# 05004586_2_PIS___2_BHC-A-2030-05__V1_0.net
KiCad netlist of a schematic drawn in Altium Designer
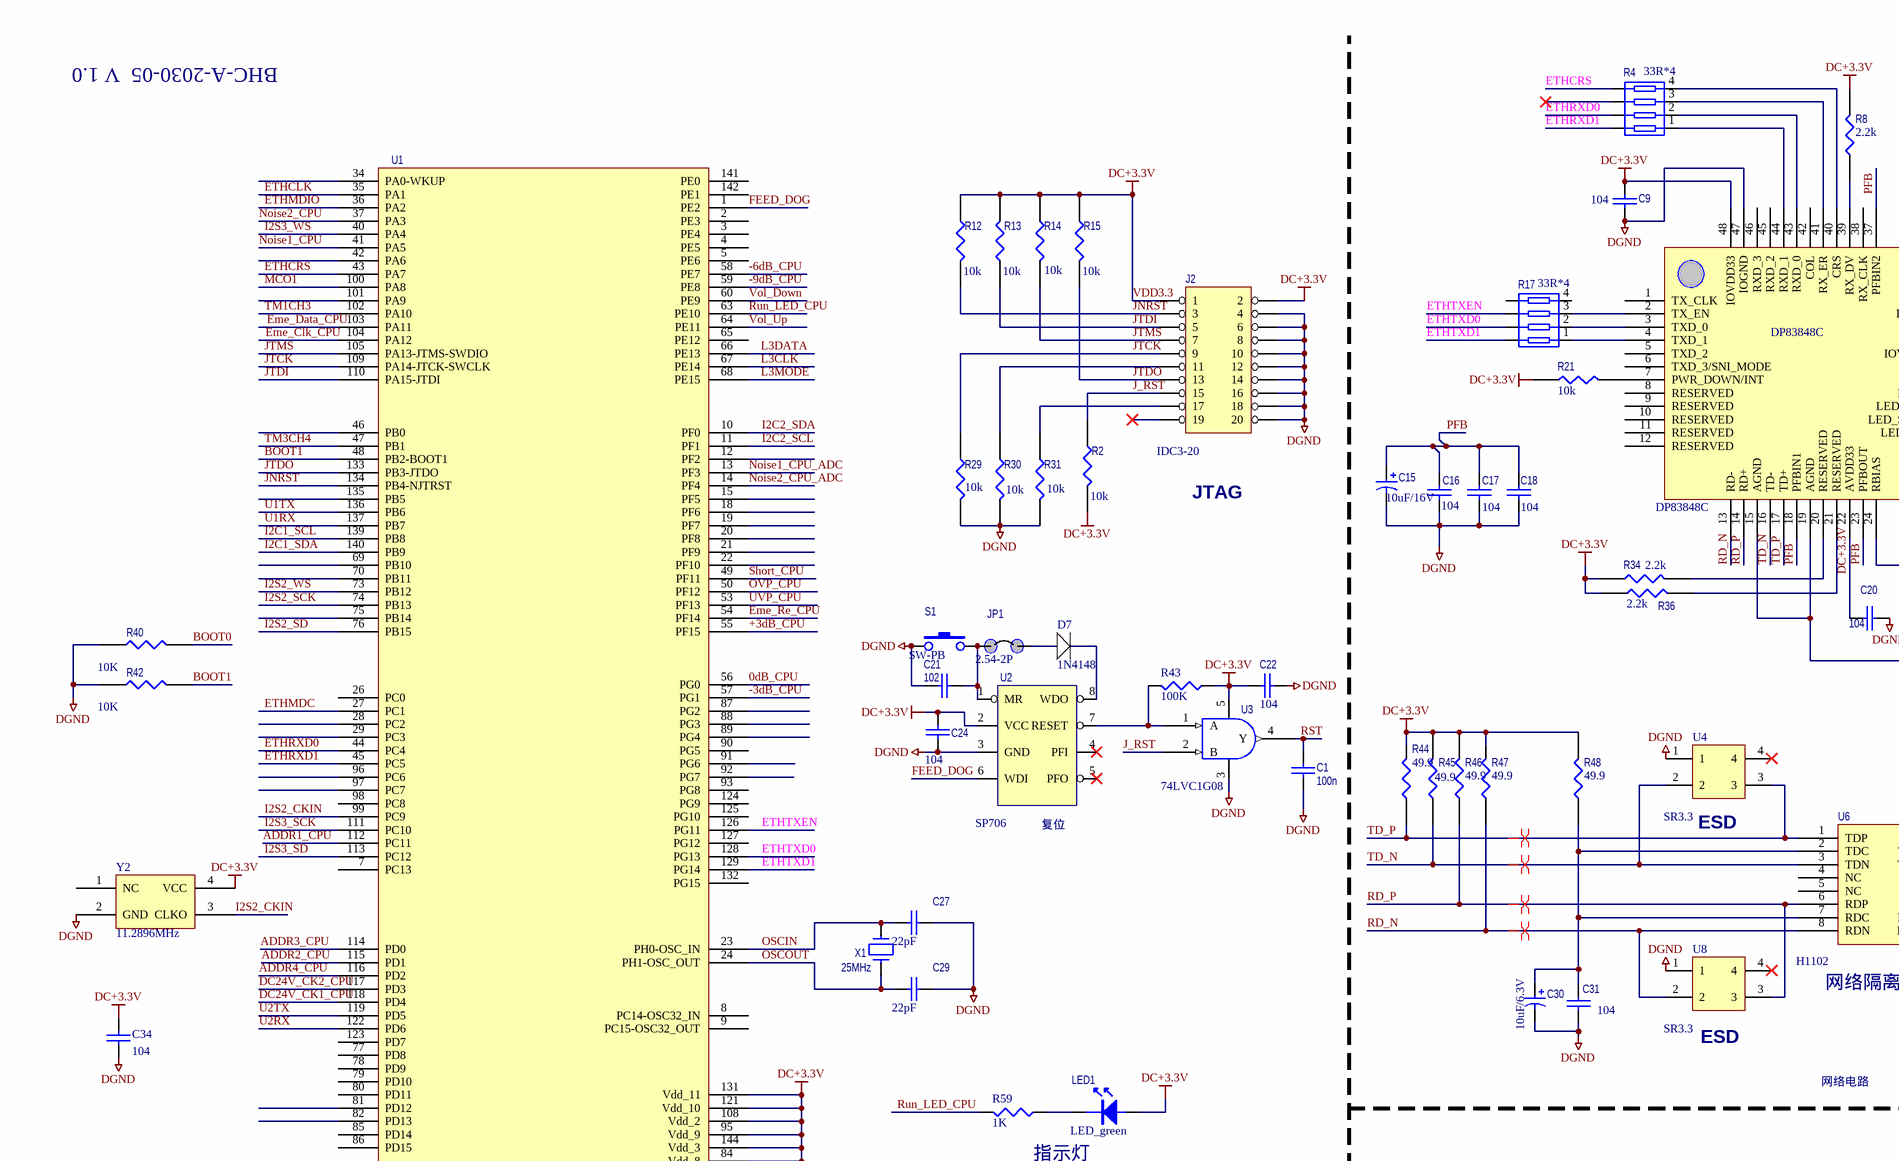
[diagram p0: 05004586宁波2号线二期车载PIS系统_功率放大器音频板2 BHC-A-2030-05_原理图 V1.0.SchDoc, top left]
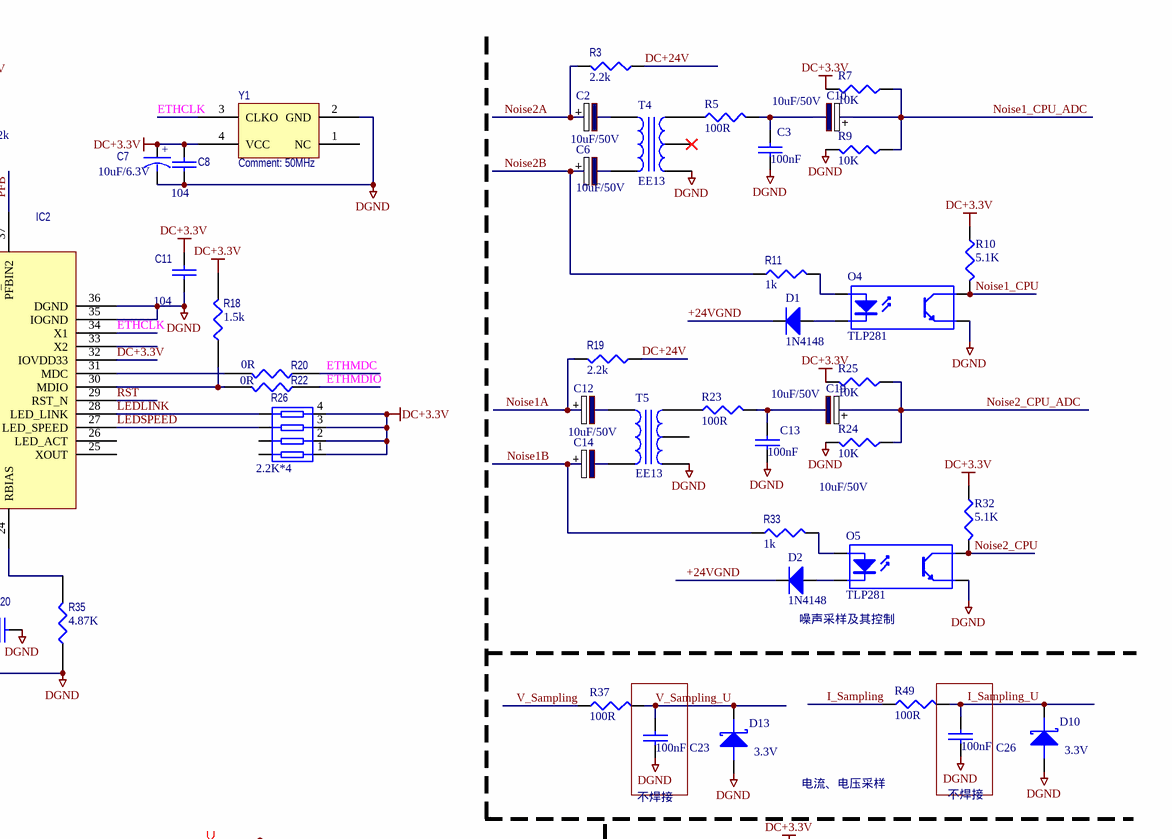
[diagram p1: 05004586宁波2号线二期车载PIS系统_功率放大器音频板2 BHC-A-2030-05_原理图 V1.0.SchDoc, top right]
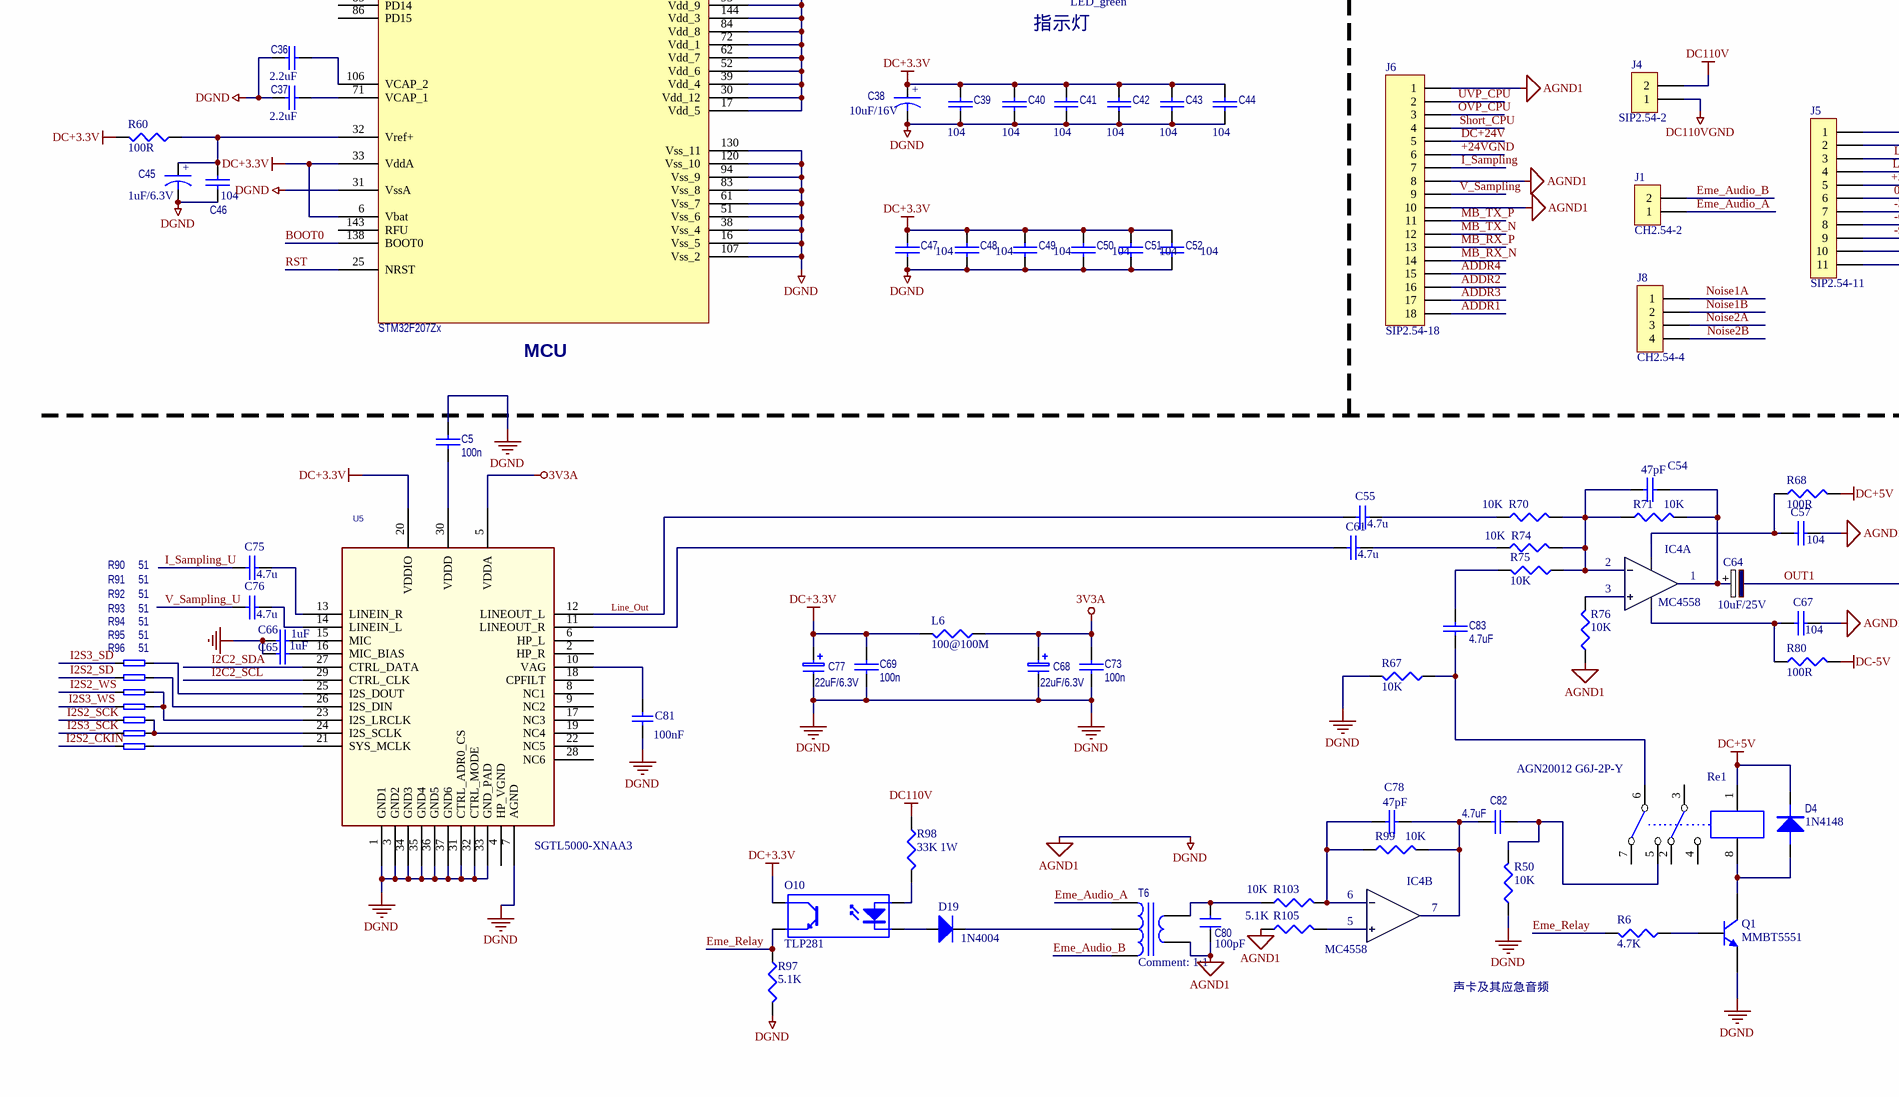
[diagram p2: 05004586宁波2号线二期车载PIS系统_功率放大器音频板2 BHC-A-2030-05_原理图 V1.0.SchDoc, bottom left]
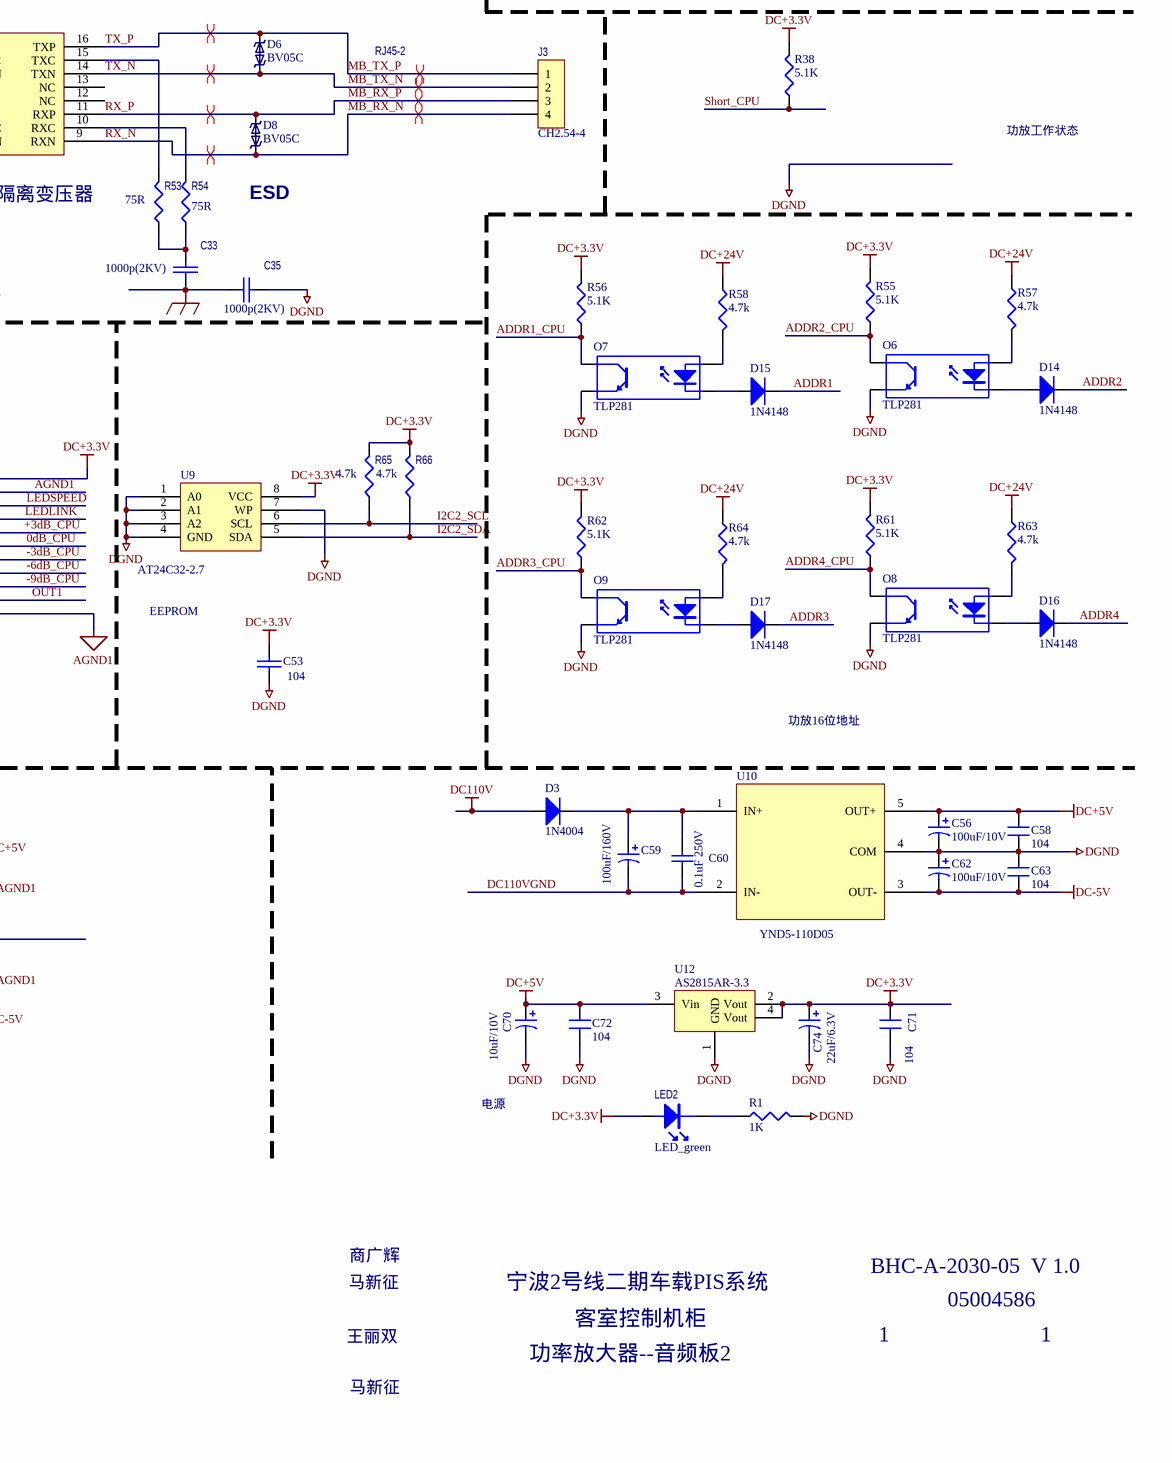
[diagram p3: 05004586宁波2号线二期车载PIS系统_功率放大器音频板2 BHC-A-2030-05_原理图 V1.0.SchDoc, bottom right]

(export (version "E")
  (design (tool "Eeschema 10.0.6"))
  (components
    (comp (ref "C1")
      (value "100n")
      (footprint "C0805")
      (description "Capacitor")
      (libsource (lib "") (part "CAP_4"))
    )
    (comp (ref "C2")
      (value "10uF/50V")
      (footprint "RB1/2")
      (fields (field (name "Comment") "10uF/25V"))
      (libsource (lib "") (part "E_1"))
    )
    (comp (ref "C3")
      (value "100nF")
      (footprint "C0805")
      (description "Capacitor")
      (libsource (lib "") (part "CAP_4"))
    )
    (comp (ref "C5")
      (value "100n")
      (footprint "C0805")
      (description "Capacitor")
      (libsource (lib "") (part "CAP_4"))
    )
    (comp (ref "C6")
      (value "10uF/50V")
      (footprint "RB1/2")
      (fields (field (name "Comment") "10uF/25V"))
      (libsource (lib "") (part "E_1"))
    )
    (comp (ref "C7")
      (value "10uF/6.3V")
      (footprint "3216A")
      (description "Capacitor")
      (libsource (lib "*") (part "CAPACITOR POL"))
    )
    (comp (ref "C8")
      (value "104")
      (footprint "C0805")
      (description "Capacitor")
      (libsource (lib "") (part "CAP_1"))
    )
    (comp (ref "C9")
      (value "104")
      (footprint "C0805")
      (description "Capacitor")
      (libsource (lib "") (part "CAP_1"))
    )
    (comp (ref "C10")
      (value "10uF/50V")
      (footprint "RB1/2")
      (fields (field (name "Comment") "10uF/25V"))
      (libsource (lib "*") (part "E"))
    )
    (comp (ref "C11")
      (value "104")
      (footprint "C0805")
      (description "Capacitor")
      (libsource (lib "") (part "CAP_1"))
    )
    (comp (ref "C12")
      (value "10uF/50V")
      (footprint "RB1/2")
      (fields (field (name "Comment") "10uF/25V"))
      (libsource (lib "") (part "E_1"))
    )
    (comp (ref "C13")
      (value "100nF")
      (footprint "C0805")
      (description "Capacitor")
      (libsource (lib "") (part "CAP_4"))
    )
    (comp (ref "C14")
      (value "10uF/50V")
      (footprint "RB1/2")
      (fields (field (name "Comment") "10uF/25V"))
      (libsource (lib "") (part "E_1"))
    )
    (comp (ref "C15")
      (value "10uF/16V")
      (footprint "CAP-B")
      (description "Bi-Polar Capacitor")
      (libsource (lib "*") (part "CAP2"))
    )
    (comp (ref "C16")
      (value "104")
      (footprint "C0805")
      (description "Capacitor")
      (libsource (lib "") (part "CAP_1"))
    )
    (comp (ref "C17")
      (value "104")
      (footprint "C0805")
      (description "Capacitor")
      (libsource (lib "") (part "CAP_1"))
    )
    (comp (ref "C18")
      (value "104")
      (footprint "C0805")
      (description "Capacitor")
      (libsource (lib "") (part "CAP_1"))
    )
    (comp (ref "C19")
      (value "10uF/50V")
      (footprint "RB1/2")
      (fields (field (name "Comment") "10uF/25V"))
      (libsource (lib "*") (part "E"))
    )
    (comp (ref "C20")
      (value "104")
      (footprint "C0805")
      (description "Capacitor")
      (libsource (lib "") (part "CAP_1"))
    )
    (comp (ref "C21")
      (value "102")
      (footprint "C0805")
      (description "Capacitor")
      (libsource (lib "") (part "CAP_2"))
    )
    (comp (ref "C22")
      (value "104")
      (footprint "C0805")
      (description "Capacitor")
      (libsource (lib "") (part "CAP_2"))
    )
    (comp (ref "C23")
      (value "100nF")
      (footprint "C0805")
      (description "Capacitor")
      (libsource (lib "") (part "CAP_4"))
    )
    (comp (ref "C24")
      (value "104")
      (footprint "C0805")
      (description "Capacitor")
      (libsource (lib "") (part "CAP_2"))
    )
    (comp (ref "C26")
      (value "100nF")
      (footprint "C0805")
      (description "Capacitor")
      (libsource (lib "") (part "CAP_4"))
    )
    (comp (ref "C27")
      (value "22pF")
      (footprint "C0805")
      (description "Capacitor")
      (libsource (lib "") (part "CAP_1"))
    )
    (comp (ref "C29")
      (value "22pF")
      (footprint "C0805")
      (description "Capacitor")
      (libsource (lib "") (part "CAP_1"))
    )
    (comp (ref "C30")
      (value "10uF/6.3V")
      (footprint "3216A")
      (description "Bi-Polar Capacitor")
      (fields (field (name "Comment") "10uF/10V"))
      (libsource (lib "*") (part "CAP2"))
    )
    (comp (ref "C31") (value "104") (footprint "C0805") (libsource (lib "*") (part "CAP")))
    (comp (ref "C33")
      (value "1000p(2KV)")
      (footprint "C1206")
      (description "Capacitor")
      (fields (field (name "ALTIUM_UNNAMED_1") "1000p(2KV)"))
      (libsource (lib "") (part "CAP_1"))
    )
    (comp (ref "C34") (value "104") (footprint "C0805") (libsource (lib "*") (part "CAP")))
    (comp (ref "C35")
      (value "1000p(2KV)")
      (footprint "C1206")
      (description "Capacitor")
      (fields (field (name "ALTIUM_UNNAMED_1") "1000p(2KV)"))
      (libsource (lib "") (part "CAP_1"))
    )
    (comp (ref "C36")
      (value "2.2uF")
      (footprint "C0805")
      (description "Capacitor")
      (libsource (lib "") (part "CAP_1"))
    )
    (comp (ref "C37")
      (value "2.2uF")
      (footprint "C0805")
      (description "Capacitor")
      (libsource (lib "") (part "CAP_1"))
    )
    (comp (ref "C38")
      (value "10uF/16V")
      (footprint "CAP-B")
      (description "Capacitor")
      (libsource (lib "*") (part "CAPACITOR POL"))
    )
    (comp (ref "C39") (value "104") (footprint "C0805") (libsource (lib "*") (part "CAP")))
    (comp (ref "C40") (value "104") (footprint "C0805") (libsource (lib "*") (part "CAP")))
    (comp (ref "C41") (value "104") (footprint "C0805") (libsource (lib "*") (part "CAP")))
    (comp (ref "C42") (value "104") (footprint "C0805") (libsource (lib "*") (part "CAP")))
    (comp (ref "C43") (value "104") (footprint "C0805") (libsource (lib "*") (part "CAP")))
    (comp (ref "C44") (value "104") (footprint "C0805") (libsource (lib "*") (part "CAP")))
    (comp (ref "C45")
      (value "1uF/6.3V")
      (footprint "3216A")
      (description "Capacitor")
      (libsource (lib "*") (part "CAPACITOR POL"))
    )
    (comp (ref "C46")
      (value "104")
      (footprint "C0805")
      (description "Capacitor")
      (libsource (lib "") (part "CAP_1"))
    )
    (comp (ref "C47") (value "104") (footprint "C0805") (libsource (lib "*") (part "CAP")))
    (comp (ref "C48") (value "104") (footprint "C0805") (libsource (lib "*") (part "CAP")))
    (comp (ref "C49") (value "104") (footprint "C0805") (libsource (lib "*") (part "CAP")))
    (comp (ref "C50") (value "104") (footprint "C0805") (libsource (lib "*") (part "CAP")))
    (comp (ref "C51") (value "104") (footprint "C0805") (libsource (lib "*") (part "CAP")))
    (comp (ref "C52") (value "104") (footprint "C0805") (libsource (lib "*") (part "CAP")))
    (comp (ref "C53")
      (value "104")
      (footprint "C0805")
      (description "Capacitor")
      (libsource (lib "") (part "CAP_2"))
    )
    (comp (ref "C54")
      (value "47pF")
      (footprint "C0805")
      (description "Capacitor")
      (libsource (lib "") (part "CAP_4"))
    )
    (comp (ref "C55")
      (value "4.7u")
      (footprint "C0805")
      (description "Capacitor")
      (fields (field (name "Comment") "104"))
      (libsource (lib "") (part "CAP_4"))
    )
    (comp (ref "C56")
      (value "100uF/10V")
      (footprint "CAP-D")
      (description "Bi-Polar Capacitor")
      (fields (field (name "Comment") "100uF/16V"))
      (libsource (lib "*") (part "CAP2"))
    )
    (comp (ref "C57")
      (value "104")
      (footprint "C0805")
      (description "Capacitor")
      (libsource (lib "") (part "CAP_4"))
    )
    (comp (ref "C58")
      (value "104")
      (footprint "C0805")
      (description "Capacitor")
      (libsource (lib "") (part "CAP_3"))
    )
    (comp (ref "C59")
      (value "100uF/160V")
      (footprint "E100")
      (description "Bi-Polar Capacitor")
      (fields (field (name "Comment") "100uF/16V"))
      (libsource (lib "*") (part "CAP2"))
    )
    (comp (ref "C60")
      (value "0.1uF 250V")
      (footprint "M1206")
      (description "Capacitor")
      (fields (field (name "PUBLISHER") "Altium Limited"))
      (libsource (lib "*") (part "Cap"))
    )
    (comp (ref "C61")
      (value "4.7u")
      (footprint "C0805")
      (description "Capacitor")
      (fields (field (name "Comment") "104"))
      (libsource (lib "") (part "CAP_4"))
    )
    (comp (ref "C62")
      (value "100uF/10V")
      (footprint "CAP-D")
      (description "Bi-Polar Capacitor")
      (fields (field (name "Comment") "100uF/16V"))
      (libsource (lib "*") (part "CAP2"))
    )
    (comp (ref "C63")
      (value "104")
      (footprint "C0805")
      (description "Capacitor")
      (libsource (lib "") (part "CAP_3"))
    )
    (comp (ref "C64") (value "10uF/25V") (footprint "RB1/2") (libsource (lib "") (part "E_1")))
    (comp (ref "C65")
      (value "1uF")
      (footprint "C0805")
      (description "Capacitor")
      (fields (field (name "PUBLISHER") "Altium Limited"))
      (libsource (lib "Miscellaneous Devices") (part "Cap"))
    )
    (comp (ref "C66")
      (value "1uF")
      (footprint "C0805")
      (description "Capacitor")
      (fields (field (name "PUBLISHER") "Altium Limited"))
      (libsource (lib "Miscellaneous Devices") (part "Cap"))
    )
    (comp (ref "C67")
      (value "104")
      (footprint "C0805")
      (description "Capacitor")
      (libsource (lib "") (part "CAP_4"))
    )
    (comp (ref "C68")
      (value "22uF/6.3V")
      (footprint "3216A")
      (description "Bi-Polar Capacitor")
      (libsource (lib "*") (part "CAPBP2"))
    )
    (comp (ref "C69")
      (value "100n")
      (footprint "C0805")
      (description "Capacitor")
      (libsource (lib "") (part "CAP_4"))
    )
    (comp (ref "C70")
      (value "10uF/10V")
      (footprint "3216A")
      (description "Bi-Polar Capacitor")
      (libsource (lib "*") (part "CAP2"))
    )
    (comp (ref "C71")
      (value "104")
      (footprint "C0805")
      (description "Capacitor")
      (libsource (lib "") (part "CAP_3"))
    )
    (comp (ref "C72")
      (value "104")
      (footprint "C0805")
      (description "Capacitor")
      (libsource (lib "") (part "CAP_3"))
    )
    (comp (ref "C73")
      (value "100n")
      (footprint "C0805")
      (description "Capacitor")
      (libsource (lib "") (part "CAP_4"))
    )
    (comp (ref "C74")
      (value "22uF/6.3V")
      (footprint "3216A")
      (description "Bi-Polar Capacitor")
      (libsource (lib "*") (part "CAP2"))
    )
    (comp (ref "C75")
      (value "4.7u")
      (footprint "C0805")
      (description "Capacitor")
      (fields (field (name "Comment") "104"))
      (libsource (lib "") (part "CAP_4"))
    )
    (comp (ref "C76")
      (value "4.7u")
      (footprint "C0805")
      (description "Capacitor")
      (fields (field (name "Comment") "104"))
      (libsource (lib "") (part "CAP_4"))
    )
    (comp (ref "C77")
      (value "22uF/6.3V")
      (footprint "3216A")
      (description "Bi-Polar Capacitor")
      (libsource (lib "*") (part "CAPBP2"))
    )
    (comp (ref "C78")
      (value "47pF")
      (footprint "C0805")
      (description "Capacitor")
      (libsource (lib "") (part "CAP_4"))
    )
    (comp (ref "C80")
      (value "100pF")
      (footprint "C0805")
      (description "Capacitor")
      (fields (field (name "Comment") "100p"))
      (libsource (lib "") (part "CAP_3"))
    )
    (comp (ref "C81")
      (value "100nF")
      (footprint "C0805")
      (description "Capacitor")
      (fields (field (name "Comment") "100n") (field (name "PUBLISHER") "Altium Limited"))
      (libsource (lib "Miscellaneous Devices") (part "Cap"))
    )
    (comp (ref "C82")
      (value "4.7uF")
      (footprint "C0805")
      (description "Capacitor")
      (libsource (lib "") (part "CAP_4"))
    )
    (comp (ref "C83")
      (value "4.7uF")
      (footprint "C0805")
      (description "Capacitor")
      (libsource (lib "") (part "CAP_4"))
    )
    (comp (ref "D1")
      (value "1N4148")
      (footprint "7227AK")
      (description "Default Diode")
      (fields (field (name "Comment") "DIODE"))
      (libsource (lib "SCH") (part "DIODE"))
    )
    (comp (ref "D2")
      (value "1N4148")
      (footprint "7227AK")
      (description "Default Diode")
      (fields (field (name "Comment") "DIODE"))
      (libsource (lib "SCH") (part "DIODE"))
    )
    (comp (ref "D3")
      (value "1N4004")
      (footprint "7227AK")
      (description "Default Diode")
      (fields (field (name "Comment") "DIODE"))
      (libsource (lib "SCH") (part "DIODE"))
    )
    (comp (ref "D4")
      (value "1N4148")
      (footprint "7227AK")
      (description "Diode")
      (fields (field (name "Comment") "1N4004"))
      (libsource (lib "*") (part "DIODE"))
    )
    (comp (ref "D6") (value "BV05C") (footprint "SOD-323") (libsource (lib "Sch") (part "BV05C")))
    (comp (ref "D7") (value "1N4148") (footprint "1206AK") (libsource (lib "*") (part "D")))
    (comp (ref "D8") (value "BV05C") (footprint "SOD-323") (libsource (lib "Sch") (part "BV05C")))
    (comp (ref "D10")
      (value "3.3V")
      (footprint "1206ak")
      (description "Schottky Diode")
      (libsource (lib "*") (part "DIODE SCHOTTKY"))
    )
    (comp (ref "D13")
      (value "3.3V")
      (footprint "1206ak")
      (description "Schottky Diode")
      (libsource (lib "*") (part "DIODE SCHOTTKY"))
    )
    (comp (ref "D14")
      (value "1N4148")
      (footprint "7227AK")
      (description "Default Diode")
      (fields (field (name "Comment") "DIODE"))
      (libsource (lib "SCH") (part "DIODE"))
    )
    (comp (ref "D15")
      (value "1N4148")
      (footprint "7227AK")
      (description "Default Diode")
      (fields (field (name "Comment") "DIODE"))
      (libsource (lib "SCH") (part "DIODE"))
    )
    (comp (ref "D16")
      (value "1N4148")
      (footprint "7227AK")
      (description "Default Diode")
      (fields (field (name "Comment") "DIODE"))
      (libsource (lib "SCH") (part "DIODE"))
    )
    (comp (ref "D17")
      (value "1N4148")
      (footprint "7227AK")
      (description "Default Diode")
      (fields (field (name "Comment") "DIODE"))
      (libsource (lib "SCH") (part "DIODE"))
    )
    (comp (ref "D19")
      (value "1N4004")
      (footprint "7227AK")
      (description "Default Diode")
      (fields (field (name "Comment") "DIODE"))
      (libsource (lib "SCH") (part "DIODE"))
    )
    (comp (ref "IC2") (value "DP83848C") (footprint "LQFP48") (libsource (lib "*") (part "DP83848C")))
    (comp (ref "IC4") (value "MC4558") (footprint "SO-8") (libsource (lib "*") (part "MC4558")))
    (comp (ref "J1")
      (value "CH2.54-2")
      (footprint "CH2.54-2")
      (description "Connector")
      (fields (field (name "Comment") "CON2"))
      (libsource (lib "SCH") (part "CON2"))
    )
    (comp (ref "J2")
      (value "IDC3-20")
      (footprint "IDC3-20")
      (fields (field (name "Comment") "IDC20"))
      (libsource (lib "*") (part "HEADER 10X2"))
    )
    (comp (ref "J3")
      (value "CH2.54-4")
      (footprint "CH2.54-4")
      (description "Connector")
      (fields (field (name "Comment") "CON4"))
      (libsource (lib "*") (part "CON4"))
    )
    (comp (ref "J4")
      (value "SIP2.54-2")
      (footprint "SIP2.54-2")
      (description "Connector")
      (fields (field (name "Comment") "CON2"))
      (libsource (lib "SCH") (part "CON2"))
    )
    (comp (ref "J5")
      (value "SIP2.54-11")
      (footprint "SIP2.54-11")
      (fields (field (name "Comment") "CON11"))
      (libsource (lib "SCH") (part "CON11"))
    )
    (comp (ref "J6")
      (value "SIP2.54-18")
      (footprint "SIP2.54-18")
      (description "Connector")
      (fields (field (name "Comment") "CON18"))
      (libsource (lib "SCH") (part "CON18"))
    )
    (comp (ref "J8")
      (value "CH2.54-4")
      (footprint "CH2.54-4")
      (fields (field (name "Comment") "CON4"))
      (libsource (lib "SCH") (part "CON4"))
    )
    (comp (ref "JP1") (value "2.54-2P") (footprint "SIP2.54-2") (libsource (lib "*") (part "TX")))
    (comp (ref "L6")
      (value "100@100M")
      (footprint "M0805")
      (description "Resistor")
      (fields (field (name "Comment") "10uH") (field (name "PUBLISHER") "Altium Limited"))
      (libsource (lib "Miscellaneous Devices") (part "Res3"))
    )
    (comp (ref "LED1") (value "LED_green") (footprint "LED(贴片)") (libsource (lib "*") (part "LED")))
    (comp (ref "LED2") (value "LED_green") (footprint "LED(贴片)") (libsource (lib "*") (part "LED")))
    (comp (ref "O4")
      (value "TLP281")
      (footprint "SOP4")
      (description "4-Pin Phototransistor Optocoupler")
      (fields (field (name "PUBLISHER") "Altium Limited"))
      (libsource (lib "Miscellaneous Devices") (part "Optoisolator1"))
    )
    (comp (ref "O5")
      (value "TLP281")
      (footprint "SOP4")
      (description "4-Pin Phototransistor Optocoupler")
      (fields (field (name "PUBLISHER") "Altium Limited"))
      (libsource (lib "Miscellaneous Devices") (part "Optoisolator1"))
    )
    (comp (ref "O6")
      (value "TLP281")
      (footprint "SOP4")
      (description "4-Pin Phototransistor Optocoupler")
      (fields (field (name "PUBLISHER") "Altium Limited"))
      (libsource (lib "Miscellaneous Devices") (part "Optoisolator1"))
    )
    (comp (ref "O7")
      (value "TLP281")
      (footprint "SOP4")
      (description "4-Pin Phototransistor Optocoupler")
      (fields (field (name "PUBLISHER") "Altium Limited"))
      (libsource (lib "Miscellaneous Devices") (part "Optoisolator1"))
    )
    (comp (ref "O8")
      (value "TLP281")
      (footprint "SOP4")
      (description "4-Pin Phototransistor Optocoupler")
      (fields (field (name "PUBLISHER") "Altium Limited"))
      (libsource (lib "Miscellaneous Devices") (part "Optoisolator1"))
    )
    (comp (ref "O9")
      (value "TLP281")
      (footprint "SOP4")
      (description "4-Pin Phototransistor Optocoupler")
      (fields (field (name "PUBLISHER") "Altium Limited"))
      (libsource (lib "Miscellaneous Devices") (part "Optoisolator1"))
    )
    (comp (ref "O10")
      (value "TLP281")
      (footprint "SOP4")
      (description "4-Pin Phototransistor Optocoupler")
      (fields (field (name "PUBLISHER") "Altium Limited"))
      (libsource (lib "Miscellaneous Devices") (part "Optoisolator1"))
    )
    (comp (ref "Q1")
      (value "MMBT5551")
      (footprint "SOT-23B_N")
      (description "NPN Bipolar Transistor")
      (fields (field (name "PUBLISHER") "Altium Limited"))
      (libsource (lib "*") (part "NPN"))
    )
    (comp (ref "R1")
      (value "1K")
      (footprint "M0805")
      (description "Resistor")
      (fields (field (name "PUBLISHER") "Altium Limited"))
      (libsource (lib "*") (part "Res3"))
    )
    (comp (ref "R2")
      (value "10k")
      (footprint "M0805")
      (fields (field (name "Comment") "10K"))
      (libsource (lib "*") (part "RES1"))
    )
    (comp (ref "R3") (value "2.2k") (footprint "M0805") (libsource (lib "") (part "RES1_1")))
    (comp (ref "R4")
      (value "33R*4")
      (footprint "PZ-4-0.8B")
      (fields (field (name "Comment") "33*4"))
      (libsource (lib "*") (part "RES-P4"))
    )
    (comp (ref "R5")
      (value "100R")
      (footprint "M0805")
      (description "Resistor")
      (fields (field (name "PUBLISHER") "Altium Limited"))
      (libsource (lib "*") (part "Res3"))
    )
    (comp (ref "R6")
      (value "4.7K")
      (footprint "M0805")
      (description "Resistor")
      (fields (field (name "Comment") "Res3") (field (name "PUBLISHER") "Altium Limited"))
      (libsource (lib "Miscellaneous Devices") (part "Res3"))
    )
    (comp (ref "R7")
      (value "10K")
      (footprint "M0805")
      (description "Resistor")
      (fields (field (name "PUBLISHER") "Altium Limited"))
      (libsource (lib "*") (part "Res3"))
    )
    (comp (ref "R8")
      (value "2.2k")
      (footprint "M0805")
      (fields (field (name "Comment") "10K"))
      (libsource (lib "*") (part "RES1"))
    )
    (comp (ref "R9")
      (value "10K")
      (footprint "M0805")
      (description "Resistor")
      (fields (field (name "PUBLISHER") "Altium Limited"))
      (libsource (lib "*") (part "Res3"))
    )
    (comp (ref "R10")
      (value "5.1K")
      (footprint "M0805")
      (description "Resistor")
      (fields (field (name "PUBLISHER") "Altium Limited"))
      (libsource (lib "*") (part "Res3"))
    )
    (comp (ref "R11") (value "1k") (footprint "M0805") (libsource (lib "") (part "RES1_1")))
    (comp (ref "R12")
      (value "10k")
      (footprint "M0805")
      (fields (field (name "Comment") "10K"))
      (libsource (lib "*") (part "RES1"))
    )
    (comp (ref "R13")
      (value "10k")
      (footprint "M0805")
      (fields (field (name "Comment") "10K"))
      (libsource (lib "*") (part "RES1"))
    )
    (comp (ref "R14")
      (value "10k")
      (footprint "M0805")
      (fields (field (name "Comment") "10K"))
      (libsource (lib "*") (part "RES1"))
    )
    (comp (ref "R15")
      (value "10k")
      (footprint "M0805")
      (fields (field (name "Comment") "10K"))
      (libsource (lib "*") (part "RES1"))
    )
    (comp (ref "R17")
      (value "33R*4")
      (footprint "PZ-4-0.8B")
      (fields (field (name "Comment") "33*4"))
      (libsource (lib "*") (part "RES-P4"))
    )
    (comp (ref "R18")
      (value "1.5k")
      (footprint "M0805")
      (fields (field (name "Comment") "10K"))
      (libsource (lib "*") (part "RES1"))
    )
    (comp (ref "R19") (value "2.2k") (footprint "M0805") (libsource (lib "") (part "RES1_1")))
    (comp (ref "R20") (value "0R") (footprint "M0805") (libsource (lib "*") (part "RES1")))
    (comp (ref "R21")
      (value "10k")
      (footprint "M0805")
      (fields (field (name "Comment") "10K"))
      (libsource (lib "*") (part "RES1"))
    )
    (comp (ref "R22") (value "0R") (footprint "M0805") (libsource (lib "*") (part "RES1")))
    (comp (ref "R23")
      (value "100R")
      (footprint "M0805")
      (description "Resistor")
      (fields (field (name "PUBLISHER") "Altium Limited"))
      (libsource (lib "*") (part "Res3"))
    )
    (comp (ref "R24")
      (value "10K")
      (footprint "M0805")
      (description "Resistor")
      (fields (field (name "PUBLISHER") "Altium Limited"))
      (libsource (lib "*") (part "Res3"))
    )
    (comp (ref "R25")
      (value "10K")
      (footprint "M0805")
      (description "Resistor")
      (fields (field (name "PUBLISHER") "Altium Limited"))
      (libsource (lib "*") (part "Res3"))
    )
    (comp (ref "R26")
      (value "~")
      (footprint "PZ-4-0.8B")
      (fields (field (name "ALTIUM_UNNAMED_1") "2.2K*4"))
      (libsource (lib "*") (part "RES-P4"))
    )
    (comp (ref "R29")
      (value "10k")
      (footprint "M0805")
      (fields (field (name "Comment") "10K"))
      (libsource (lib "*") (part "RES1"))
    )
    (comp (ref "R30")
      (value "10k")
      (footprint "M0805")
      (fields (field (name "Comment") "10K"))
      (libsource (lib "*") (part "RES1"))
    )
    (comp (ref "R31")
      (value "10k")
      (footprint "M0805")
      (fields (field (name "Comment") "10K"))
      (libsource (lib "*") (part "RES1"))
    )
    (comp (ref "R32")
      (value "5.1K")
      (footprint "M0805")
      (description "Resistor")
      (fields (field (name "PUBLISHER") "Altium Limited"))
      (libsource (lib "*") (part "Res3"))
    )
    (comp (ref "R33") (value "1k") (footprint "M0805") (libsource (lib "") (part "RES1_1")))
    (comp (ref "R34")
      (value "2.2k")
      (footprint "M0805")
      (fields (field (name "Comment") "10K"))
      (libsource (lib "*") (part "RES1"))
    )
    (comp (ref "R35") (value "4.87K") (footprint "M0805") (libsource (lib "*") (part "RES1")))
    (comp (ref "R36")
      (value "2.2k")
      (footprint "M0805")
      (fields (field (name "Comment") "10K"))
      (libsource (lib "*") (part "RES1"))
    )
    (comp (ref "R37")
      (value "100R")
      (footprint "M0805")
      (description "Resistor")
      (fields (field (name "PUBLISHER") "Altium Limited"))
      (libsource (lib "*") (part "Res3"))
    )
    (comp (ref "R38")
      (value "5.1K")
      (footprint "M0805")
      (description "Resistor")
      (fields (field (name "PUBLISHER") "Altium Limited"))
      (libsource (lib "*") (part "Res3"))
    )
    (comp (ref "R40") (value "10K") (footprint "M0805") (libsource (lib "*") (part "RES1")))
    (comp (ref "R42") (value "10K") (footprint "M0805") (libsource (lib "*") (part "RES1")))
    (comp (ref "R43")
      (value "100K")
      (footprint "M0805")
      (description "Resistor")
      (fields (field (name "PUBLISHER") "Altium Limited"))
      (libsource (lib "*") (part "Res3"))
    )
    (comp (ref "R44") (value "49.9") (footprint "M0805") (libsource (lib "*") (part "RES1")))
    (comp (ref "R45") (value "49.9") (footprint "M0805") (libsource (lib "*") (part "RES1")))
    (comp (ref "R46") (value "49.9") (footprint "M0805") (libsource (lib "*") (part "RES1")))
    (comp (ref "R47") (value "49.9") (footprint "M0805") (libsource (lib "*") (part "RES1")))
    (comp (ref "R48") (value "49.9") (footprint "M0805") (libsource (lib "*") (part "RES1")))
    (comp (ref "R49")
      (value "100R")
      (footprint "M0805")
      (description "Resistor")
      (fields (field (name "PUBLISHER") "Altium Limited"))
      (libsource (lib "*") (part "Res3"))
    )
    (comp (ref "R50")
      (value "10K")
      (footprint "M0805")
      (description "Resistor")
      (fields (field (name "Comment") "10k") (field (name "PUBLISHER") "Altium Limited"))
      (libsource (lib "Miscellaneous Devices") (part "Res3"))
    )
    (comp (ref "R53") (value "75R") (footprint "M0805") (libsource (lib "") (part "RES1_1")))
    (comp (ref "R54") (value "75R") (footprint "M0805") (libsource (lib "") (part "RES1_1")))
    (comp (ref "R55")
      (value "5.1K")
      (footprint "M0805")
      (description "Resistor")
      (fields (field (name "PUBLISHER") "Altium Limited"))
      (libsource (lib "*") (part "Res3"))
    )
    (comp (ref "R56")
      (value "5.1K")
      (footprint "M0805")
      (description "Resistor")
      (fields (field (name "PUBLISHER") "Altium Limited"))
      (libsource (lib "*") (part "Res3"))
    )
    (comp (ref "R57")
      (value "4.7k")
      (footprint "M1206")
      (description "Resistor")
      (fields (field (name "PUBLISHER") "Altium Limited"))
      (libsource (lib "Miscellaneous Devices") (part "Res3"))
    )
    (comp (ref "R58")
      (value "4.7k")
      (footprint "M1206")
      (description "Resistor")
      (fields (field (name "PUBLISHER") "Altium Limited"))
      (libsource (lib "Miscellaneous Devices") (part "Res3"))
    )
    (comp (ref "R59")
      (value "1K")
      (footprint "M0805")
      (description "Resistor")
      (fields (field (name "PUBLISHER") "Altium Limited"))
      (libsource (lib "*") (part "Res3"))
    )
    (comp (ref "R60")
      (value "100R")
      (footprint "M0805")
      (description "Resistor")
      (fields (field (name "PUBLISHER") "Altium Limited"))
      (libsource (lib "*") (part "Res3"))
    )
    (comp (ref "R61")
      (value "5.1K")
      (footprint "M0805")
      (description "Resistor")
      (fields (field (name "PUBLISHER") "Altium Limited"))
      (libsource (lib "*") (part "Res3"))
    )
    (comp (ref "R62")
      (value "5.1K")
      (footprint "M0805")
      (description "Resistor")
      (fields (field (name "PUBLISHER") "Altium Limited"))
      (libsource (lib "*") (part "Res3"))
    )
    (comp (ref "R63")
      (value "4.7k")
      (footprint "M1206")
      (description "Resistor")
      (fields (field (name "PUBLISHER") "Altium Limited"))
      (libsource (lib "Miscellaneous Devices") (part "Res3"))
    )
    (comp (ref "R64")
      (value "4.7k")
      (footprint "M1206")
      (description "Resistor")
      (fields (field (name "PUBLISHER") "Altium Limited"))
      (libsource (lib "Miscellaneous Devices") (part "Res3"))
    )
    (comp (ref "R65") (value "4.7k") (footprint "M0805") (libsource (lib "") (part "RES1_1")))
    (comp (ref "R66") (value "4.7k") (footprint "M0805") (libsource (lib "") (part "RES1_1")))
    (comp (ref "R67")
      (value "10K")
      (footprint "M0805")
      (description "Resistor")
      (fields (field (name "Comment") "10k") (field (name "PUBLISHER") "Altium Limited"))
      (libsource (lib "Miscellaneous Devices") (part "Res3"))
    )
    (comp (ref "R68")
      (value "100R")
      (footprint "M0805")
      (description "Resistor")
      (fields (field (name "PUBLISHER") "Altium Limited"))
      (libsource (lib "Miscellaneous Devices") (part "Res3"))
    )
    (comp (ref "R70")
      (value "10K")
      (footprint "M0805")
      (description "Resistor")
      (fields (field (name "Comment") "15k") (field (name "PUBLISHER") "Altium Limited"))
      (libsource (lib "Miscellaneous Devices") (part "Res3"))
    )
    (comp (ref "R71")
      (value "10K")
      (footprint "M0805")
      (description "Resistor")
      (fields (field (name "Comment") "11k") (field (name "PUBLISHER") "Altium Limited"))
      (libsource (lib "Miscellaneous Devices") (part "Res3"))
    )
    (comp (ref "R74")
      (value "10K")
      (footprint "M0805")
      (description "Resistor")
      (fields (field (name "Comment") "10k") (field (name "PUBLISHER") "Altium Limited"))
      (libsource (lib "Miscellaneous Devices") (part "Res3"))
    )
    (comp (ref "R75")
      (value "10K")
      (footprint "M0805")
      (description "Resistor")
      (fields (field (name "Comment") "10k") (field (name "PUBLISHER") "Altium Limited"))
      (libsource (lib "Miscellaneous Devices") (part "Res3"))
    )
    (comp (ref "R76")
      (value "10K")
      (footprint "M0805")
      (description "Resistor")
      (fields (field (name "Comment") "10k") (field (name "PUBLISHER") "Altium Limited"))
      (libsource (lib "Miscellaneous Devices") (part "Res3"))
    )
    (comp (ref "R80")
      (value "100R")
      (footprint "M0805")
      (description "Resistor")
      (fields (field (name "PUBLISHER") "Altium Limited"))
      (libsource (lib "Miscellaneous Devices") (part "Res3"))
    )
    (comp (ref "R90") (value "51") (footprint "M0805") (libsource (lib "*") (part "R")))
    (comp (ref "R91") (value "51") (footprint "M0805") (libsource (lib "*") (part "R")))
    (comp (ref "R92") (value "51") (footprint "M0805") (libsource (lib "*") (part "R")))
    (comp (ref "R93") (value "51") (footprint "M0805") (libsource (lib "*") (part "R")))
    (comp (ref "R94") (value "51") (footprint "M0805") (libsource (lib "*") (part "R")))
    (comp (ref "R95") (value "51") (footprint "M0805") (libsource (lib "*") (part "R")))
    (comp (ref "R96") (value "51") (footprint "M0805") (libsource (lib "*") (part "R")))
    (comp (ref "R97")
      (value "5.1K")
      (footprint "M0805")
      (description "Resistor")
      (fields (field (name "PUBLISHER") "Altium Limited"))
      (libsource (lib "*") (part "Res3"))
    )
    (comp (ref "R98")
      (value "33K 1W")
      (footprint "1T-2512")
      (description "Resistor")
      (fields (field (name "PUBLISHER") "Altium Limited"))
      (libsource (lib "Miscellaneous Devices") (part "Res3"))
    )
    (comp (ref "R99")
      (value "10K")
      (footprint "M0805")
      (description "Resistor")
      (fields (field (name "Comment") "11k") (field (name "PUBLISHER") "Altium Limited"))
      (libsource (lib "Miscellaneous Devices") (part "Res3"))
    )
    (comp (ref "R103")
      (value "10K")
      (footprint "M0805")
      (description "Resistor")
      (fields (field (name "Comment") "10k") (field (name "PUBLISHER") "Altium Limited"))
      (libsource (lib "Miscellaneous Devices") (part "Res3"))
    )
    (comp (ref "R105")
      (value "5.1K")
      (footprint "M0805")
      (description "Resistor")
      (fields (field (name "Comment") "10k") (field (name "PUBLISHER") "Altium Limited"))
      (libsource (lib "Miscellaneous Devices") (part "Res3"))
    )
    (comp (ref "Re1")
      (value "AGN20012 G6J-2P-Y")
      (footprint "G6J-2P")
      (libsource (lib "SCH") (part "G6J-2P"))
    )
    (comp (ref "S1") (value "SW-PB") (footprint "KEY-6A") (libsource (lib "*") (part "SW-PB")))
    (comp (ref "T4") (value "EE13") (footprint "EE13-C") (libsource (lib "SCH") (part "EE13")))
    (comp (ref "T5") (value "EE13") (footprint "EE13-C") (libsource (lib "SCH") (part "EE13")))
    (comp (ref "T6") (value "1:1") (footprint "EE13-C") (libsource (lib "*") (part "TRANS7")))
    (comp (ref "U1") (value "STM32F207Zx") (footprint "LQFP144") (libsource (lib "*") (part "STM32F207Zx")))
    (comp (ref "U2")
      (value "SP706")
      (footprint "so-8")
      (fields (field (name "Comment") "MAX706R"))
      (libsource (lib "*") (part "MAX706R"))
    )
    (comp (ref "U3") (value "74LVC1G08") (footprint "SOT-23-5+") (libsource (lib "*") (part "74LVC1G08")))
    (comp (ref "U4") (value "SR3.3") (footprint "SOT-143") (libsource (lib "*") (part "SR3.3")))
    (comp (ref "U5")
      (value "SGTL5000-XNAA3")
      (footprint "QFN32")
      (fields (field (name "Comment") "SGTL5000-XNAA3_0"))
      (libsource (lib "PCB_Project1") (part "SGTL5000-XNAA3_0"))
    )
    (comp (ref "U6") (value "H1102") (footprint "SOP-16") (libsource (lib "*") (part "H1102")))
    (comp (ref "U8") (value "SR3.3") (footprint "SOT-143") (libsource (lib "*") (part "SR3.3")))
    (comp (ref "U9") (value "AT24C32-2.7") (footprint "SO-8") (libsource (lib "*") (part "AT24C32")))
    (comp (ref "U10")
      (value "YND5-110D05")
      (footprint "YND5-48D12")
      (libsource (lib "*") (part "YND5-48D12"))
    )
    (comp (ref "U12") (value "AS2815AR-3.3") (footprint "TO-252-1") (libsource (lib "*") (part "LT1085")))
    (comp (ref "X1")
      (value "25MHz")
      (footprint "XTAL-D")
      (description "Crystal")
      (libsource (lib "*") (part "CRYSTAL"))
    )
    (comp (ref "Y1") (value "50MHz") (footprint "XTAL-XO53") (libsource (lib "*") (part "XTAL")))
    (comp (ref "Y2") (value "11.2896MHz") (footprint "XTAL-XO53") (libsource (lib "") (part "XTAL_1")))
  )
  (nets
    (net (code "1") (name "/+3dB_CPU") (class "Default")
      (node (ref "J5") (pin "5") (pinfunction "5_5") (pintype "passive"))
      (node (ref "U1") (pin "55") (pinfunction "PF15_55") (pintype "passive"))
    )
    (net (code "2") (name "/+24VGND") (class "Default")
      (node (ref "D1") (pin "K") (pinfunction "2_K") (pintype "passive"))
      (node (ref "D2") (pin "K") (pinfunction "2_K") (pintype "passive"))
      (node (ref "J6") (pin "6") (pinfunction "6_6") (pintype "passive"))
    )
    (net (code "3") (name "/-3dB_CPU") (class "Default")
      (node (ref "J5") (pin "7") (pinfunction "7_7") (pintype "passive"))
      (node (ref "U1") (pin "57") (pinfunction "PG1_57") (pintype "passive"))
    )
    (net (code "4") (name "/-6dB_CPU") (class "Default")
      (node (ref "J5") (pin "8") (pinfunction "8_8") (pintype "passive"))
      (node (ref "U1") (pin "58") (pinfunction "PE7_58") (pintype "passive"))
    )
    (net (code "5") (name "/-9dB_CPU") (class "Default")
      (node (ref "J5") (pin "9") (pinfunction "9_9") (pintype "passive"))
      (node (ref "U1") (pin "59") (pinfunction "PE8_59") (pintype "passive"))
    )
    (net (code "6") (name "/0dB_CPU") (class "Default")
      (node (ref "J5") (pin "6") (pinfunction "6_6") (pintype "passive"))
      (node (ref "U1") (pin "56") (pinfunction "PG0_56") (pintype "passive"))
    )
    (net (code "7") (name "/ADDR1") (class "Default")
      (node (ref "D15") (pin "K") (pinfunction "2_K") (pintype "passive"))
      (node (ref "J6") (pin "18") (pinfunction "18_18") (pintype "passive"))
    )
    (net (code "8") (name "/ADDR1_CPU") (class "Default")
      (node (ref "O7") (pin "4") (pinfunction "C_4") (pintype "passive"))
      (node (ref "R56") (pin "2") (pinfunction "2_2") (pintype "passive"))
      (node (ref "U1") (pin "112") (pinfunction "PC11_112") (pintype "passive"))
    )
    (net (code "9") (name "/ADDR2") (class "Default")
      (node (ref "D14") (pin "K") (pinfunction "2_K") (pintype "passive"))
      (node (ref "J6") (pin "16") (pinfunction "16_16") (pintype "passive"))
    )
    (net (code "10") (name "/ADDR2_CPU") (class "Default")
      (node (ref "O6") (pin "4") (pinfunction "C_4") (pintype "passive"))
      (node (ref "R55") (pin "2") (pinfunction "2_2") (pintype "passive"))
      (node (ref "U1") (pin "115") (pinfunction "PD1_115") (pintype "passive"))
    )
    (net (code "11") (name "/ADDR3") (class "Default")
      (node (ref "D17") (pin "K") (pinfunction "2_K") (pintype "passive"))
      (node (ref "J6") (pin "17") (pinfunction "17_17") (pintype "passive"))
    )
    (net (code "12") (name "/ADDR3_CPU") (class "Default")
      (node (ref "O9") (pin "4") (pinfunction "C_4") (pintype "passive"))
      (node (ref "R62") (pin "2") (pinfunction "2_2") (pintype "passive"))
      (node (ref "U1") (pin "114") (pinfunction "PD0_114") (pintype "passive"))
    )
    (net (code "13") (name "/ADDR4") (class "Default")
      (node (ref "D16") (pin "K") (pinfunction "2_K") (pintype "passive"))
      (node (ref "J6") (pin "15") (pinfunction "15_15") (pintype "passive"))
    )
    (net (code "14") (name "/ADDR4_CPU") (class "Default")
      (node (ref "O8") (pin "4") (pinfunction "C_4") (pintype "passive"))
      (node (ref "R61") (pin "2") (pinfunction "2_2") (pintype "passive"))
      (node (ref "U1") (pin "116") (pinfunction "PD2_116") (pintype "passive"))
    )
    (net (code "15") (name "/BOOT0") (class "Default")
      (node (ref "R40") (pin "1") (pinfunction "1_1") (pintype "passive"))
      (node (ref "U1") (pin "138") (pinfunction "BOOT0_138") (pintype "passive"))
    )
    (net (code "16") (name "/BOOT1") (class "Default")
      (node (ref "R42") (pin "1") (pinfunction "1_1") (pintype "passive"))
      (node (ref "U1") (pin "48") (pinfunction "PB2-BOOT1_48") (pintype "passive"))
    )
    (net (code "17") (name "/DC24V_CK1_CPU") (class "Default")
      (node (ref "U1") (pin "118") (pinfunction "PD4_118") (pintype "passive"))
    )
    (net (code "18") (name "/DC24V_CK2_CPU") (class "Default")
      (node (ref "U1") (pin "117") (pinfunction "PD3_117") (pintype "passive"))
    )
    (net (code "19") (name "/ETHCLK") (class "Default")
      (node (ref "IC2") (pin "34") (pinfunction "X1_34") (pintype "passive"))
      (node (ref "U1") (pin "35") (pinfunction "PA1_35") (pintype "passive"))
      (node (ref "Y1") (pin "3") (pinfunction "CLKO_3") (pintype "passive"))
    )
    (net (code "20") (name "/ETHCRS") (class "Default")
      (node (ref "R4") (pin "5") (pinfunction "5_5") (pintype "passive"))
      (node (ref "U1") (pin "43") (pinfunction "PA7_43") (pintype "passive"))
    )
    (net (code "21") (name "/ETHMDC") (class "Default")
      (node (ref "R20") (pin "2") (pinfunction "2_2") (pintype "passive"))
      (node (ref "U1") (pin "27") (pinfunction "PC1_27") (pintype "passive"))
    )
    (net (code "22") (name "/ETHMDIO") (class "Default")
      (node (ref "R22") (pin "2") (pinfunction "2_2") (pintype "passive"))
      (node (ref "U1") (pin "36") (pinfunction "PA2_36") (pintype "passive"))
    )
    (net (code "23") (name "/ETHRXD0") (class "Default")
      (node (ref "R4") (pin "7") (pinfunction "7_7") (pintype "passive"))
      (node (ref "U1") (pin "44") (pinfunction "PC4_44") (pintype "passive"))
    )
    (net (code "24") (name "/ETHRXD1") (class "Default")
      (node (ref "R4") (pin "8") (pinfunction "8_8") (pintype "passive"))
      (node (ref "U1") (pin "45") (pinfunction "PC5_45") (pintype "passive"))
    )
    (net (code "25") (name "/ETHTXD0") (class "Default")
      (node (ref "R17") (pin "7") (pinfunction "7_7") (pintype "passive"))
      (node (ref "U1") (pin "128") (pinfunction "PG13_128") (pintype "passive"))
    )
    (net (code "26") (name "/ETHTXD1") (class "Default")
      (node (ref "R17") (pin "8") (pinfunction "8_8") (pintype "passive"))
      (node (ref "U1") (pin "129") (pinfunction "PG14_129") (pintype "passive"))
    )
    (net (code "27") (name "/ETHTXEN") (class "Default")
      (node (ref "R17") (pin "6") (pinfunction "6_6") (pintype "passive"))
      (node (ref "U1") (pin "126") (pinfunction "PG11_126") (pintype "passive"))
    )
    (net (code "28") (name "/Eme_Audio_A") (class "Default")
      (node (ref "J1") (pin "1") (pinfunction "1_1") (pintype "passive"))
      (node (ref "T6") (pin "5") (pintype "passive"))
    )
    (net (code "29") (name "/Eme_Audio_B") (class "Default")
      (node (ref "J1") (pin "2") (pinfunction "2_2") (pintype "passive"))
      (node (ref "T6") (pin "3") (pintype "passive"))
    )
    (net (code "30") (name "/Eme_Clk_CPU") (class "Default")
      (node (ref "U1") (pin "104") (pinfunction "PA12_104") (pintype "passive"))
    )
    (net (code "31") (name "/Eme_Data_CPU") (class "Default")
      (node (ref "U1") (pin "103") (pinfunction "PA11_103") (pintype "passive"))
    )
    (net (code "32") (name "/Eme_Re_CPU") (class "Default")
      (node (ref "U1") (pin "54") (pinfunction "PF14_54") (pintype "passive"))
    )
    (net (code "33") (name "/Eme_Relay") (class "Default")
      (node (ref "O10") (pin "3") (pinfunction "E_3") (pintype "passive"))
      (node (ref "R6") (pin "1") (pinfunction "1_1") (pintype "passive"))
      (node (ref "R97") (pin "2") (pinfunction "2_2") (pintype "passive"))
    )
    (net (code "34") (name "/FEED_DOG") (class "Default")
      (node (ref "U1") (pin "1") (pinfunction "PE2_1") (pintype "passive"))
      (node (ref "U2") (pin "6") (pinfunction "WDI_6") (pintype "passive"))
    )
    (net (code "35") (name "/I2C1_SCL") (class "Default")
      (node (ref "U1") (pin "139") (pinfunction "PB8_139") (pintype "passive"))
    )
    (net (code "36") (name "/I2C1_SDA") (class "Default")
      (node (ref "U1") (pin "140") (pinfunction "PB9_140") (pintype "passive"))
    )
    (net (code "37") (name "/I2C2_SCL") (class "Default")
      (node (ref "R65") (pin "2") (pinfunction "2_2") (pintype "passive"))
      (node (ref "U1") (pin "11") (pinfunction "PF1_11") (pintype "passive"))
      (node (ref "U5") (pin "29") (pinfunction "CTRL_CLK_29") (pintype "passive"))
      (node (ref "U9") (pin "6") (pinfunction "SCL_6") (pintype "passive"))
    )
    (net (code "38") (name "/I2C2_SDA") (class "Default")
      (node (ref "R66") (pin "2") (pinfunction "2_2") (pintype "passive"))
      (node (ref "U1") (pin "10") (pinfunction "PF0_10") (pintype "passive"))
      (node (ref "U5") (pin "27") (pinfunction "CTRL_DATA_27") (pintype "passive"))
      (node (ref "U9") (pin "5") (pinfunction "SDA_5") (pintype "passive"))
    )
    (net (code "39") (name "/I2S2_CKIN") (class "Default")
      (node (ref "R96") (pin "1") (pinfunction "1_1") (pintype "passive"))
      (node (ref "U1") (pin "99") (pinfunction "PC9_99") (pintype "passive"))
      (node (ref "Y2") (pin "3") (pinfunction "CLKO_3") (pintype "passive"))
    )
    (net (code "40") (name "/I2S2_SCK") (class "Default")
      (node (ref "R94") (pin "1") (pinfunction "1_1") (pintype "passive"))
      (node (ref "U1") (pin "74") (pinfunction "PB13_74") (pintype "passive"))
    )
    (net (code "41") (name "/I2S2_SD") (class "Default")
      (node (ref "R91") (pin "1") (pinfunction "1_1") (pintype "passive"))
      (node (ref "U1") (pin "76") (pinfunction "PB15_76") (pintype "passive"))
    )
    (net (code "42") (name "/I2S2_WS") (class "Default")
      (node (ref "R92") (pin "1") (pinfunction "1_1") (pintype "passive"))
      (node (ref "U1") (pin "73") (pinfunction "PB12_73") (pintype "passive"))
    )
    (net (code "43") (name "/I2S3_SCK") (class "Default")
      (node (ref "R95") (pin "1") (pinfunction "1_1") (pintype "passive"))
      (node (ref "U1") (pin "111") (pinfunction "PC10_111") (pintype "passive"))
    )
    (net (code "44") (name "/I2S3_SD") (class "Default")
      (node (ref "R90") (pin "1") (pinfunction "1_1") (pintype "passive"))
      (node (ref "U1") (pin "113") (pinfunction "PC12_113") (pintype "passive"))
    )
    (net (code "45") (name "/I2S3_WS") (class "Default")
      (node (ref "R93") (pin "1") (pinfunction "1_1") (pintype "passive"))
      (node (ref "U1") (pin "40") (pinfunction "PA4_40") (pintype "passive"))
    )
    (net (code "46") (name "/I_Sampling") (class "Default")
      (node (ref "J6") (pin "7") (pinfunction "7_7") (pintype "passive"))
      (node (ref "R49") (pin "1") (pinfunction "1_1") (pintype "passive"))
    )
    (net (code "47") (name "/I_Sampling_U") (class "Default")
      (node (ref "C26") (pin "2") (pinfunction "2_2") (pintype "passive"))
      (node (ref "C75") (pin "2") (pinfunction "2_2") (pintype "passive"))
      (node (ref "D10") (pin "K") (pinfunction "K_K") (pintype "passive"))
      (node (ref "R49") (pin "2") (pinfunction "2_2") (pintype "passive"))
    )
    (net (code "48") (name "/JNRST") (class "Default")
      (node (ref "J2") (pin "3") (pinfunction "3_3") (pintype "passive"))
      (node (ref "R12") (pin "1") (pinfunction "1_1") (pintype "passive"))
      (node (ref "U1") (pin "134") (pinfunction "PB4-NJTRST_134") (pintype "passive"))
    )
    (net (code "49") (name "/JTCK") (class "Default")
      (node (ref "J2") (pin "9") (pinfunction "9_9") (pintype "passive"))
      (node (ref "R29") (pin "2") (pinfunction "2_2") (pintype "passive"))
      (node (ref "U1") (pin "109") (pinfunction "PA14-JTCK-SWCLK_109") (pintype "passive"))
    )
    (net (code "50") (name "/JTDI") (class "Default")
      (node (ref "J2") (pin "5") (pinfunction "5_5") (pintype "passive"))
      (node (ref "R13") (pin "2") (pinfunction "2_2") (pintype "passive"))
      (node (ref "U1") (pin "110") (pinfunction "PA15-JTDI_110") (pintype "passive"))
    )
    (net (code "51") (name "/JTDO") (class "Default")
      (node (ref "J2") (pin "13") (pinfunction "13_13") (pintype "passive"))
      (node (ref "R15") (pin "1") (pinfunction "1_1") (pintype "passive"))
      (node (ref "U1") (pin "133") (pinfunction "PB3-JTDO_133") (pintype "passive"))
    )
    (net (code "52") (name "/JTMS") (class "Default")
      (node (ref "J2") (pin "7") (pinfunction "7_7") (pintype "passive"))
      (node (ref "R14") (pin "1") (pinfunction "1_1") (pintype "passive"))
      (node (ref "U1") (pin "105") (pinfunction "PA13-JTMS-SWDIO_105") (pintype "passive"))
    )
    (net (code "53") (name "/J_RST") (class "Default")
      (node (ref "J2") (pin "15") (pinfunction "15_15") (pintype "passive"))
      (node (ref "R2") (pin "2") (pinfunction "2_2") (pintype "passive"))
      (node (ref "U3") (pin "2") (pinfunction "B_2") (pintype "input"))
    )
    (net (code "54") (name "/L3CLK") (class "Default")
      (node (ref "U1") (pin "67") (pinfunction "PE14_67") (pintype "passive"))
    )
    (net (code "55") (name "/L3DATA") (class "Default")
      (node (ref "U1") (pin "66") (pinfunction "PE13_66") (pintype "passive"))
    )
    (net (code "56") (name "/L3MODE") (class "Default")
      (node (ref "U1") (pin "68") (pinfunction "PE15_68") (pintype "passive"))
    )
    (net (code "57") (name "/LEDLINK") (class "Default")
      (node (ref "IC2") (pin "28") (pinfunction "LED_LINK_28") (pintype "passive"))
      (node (ref "J5") (pin "4") (pinfunction "4_4") (pintype "passive"))
      (node (ref "R26") (pin "5") (pinfunction "5_5") (pintype "passive"))
    )
    (net (code "58") (name "/LEDSPEED") (class "Default")
      (node (ref "IC2") (pin "27") (pinfunction "LED_SPEED_27") (pintype "passive"))
      (node (ref "J5") (pin "3") (pinfunction "3_3") (pintype "passive"))
      (node (ref "R26") (pin "6") (pinfunction "6_6") (pintype "passive"))
    )
    (net (code "59") (name "/Line_Out") (class "Default")
      (node (ref "C55") (pin "2") (pinfunction "2_2") (pintype "passive"))
      (node (ref "U5") (pin "12") (pinfunction "LINEOUT_L_12") (pintype "passive"))
    )
    (net (code "60") (name "/MB_RX_N") (class "Default")
      (node (ref "D8") (pin "A") (pinfunction "1_A") (pintype "passive"))
      (node (ref "J3") (pin "4") (pinfunction "4_4") (pintype "passive"))
      (node (ref "J6") (pin "14") (pinfunction "14_14") (pintype "passive"))
      (node (ref "U6") (pin "9") (pinfunction "RXN_9") (pintype "passive"))
    )
    (net (code "61") (name "/MB_RX_P") (class "Default")
      (node (ref "D8") (pin "K") (pinfunction "2_K") (pintype "passive"))
      (node (ref "J3") (pin "3") (pinfunction "3_3") (pintype "passive"))
      (node (ref "J6") (pin "13") (pinfunction "13_13") (pintype "passive"))
      (node (ref "U6") (pin "11") (pinfunction "RXP_11") (pintype "passive"))
    )
    (net (code "62") (name "/MB_TX_N") (class "Default")
      (node (ref "D6") (pin "A") (pinfunction "1_A") (pintype "passive"))
      (node (ref "J3") (pin "2") (pinfunction "2_2") (pintype "passive"))
      (node (ref "J6") (pin "12") (pinfunction "12_12") (pintype "passive"))
      (node (ref "U6") (pin "14") (pinfunction "TXN_14") (pintype "passive"))
    )
    (net (code "63") (name "/MB_TX_P") (class "Default")
      (node (ref "D6") (pin "K") (pinfunction "2_K") (pintype "passive"))
      (node (ref "J3") (pin "1") (pinfunction "1_1") (pintype "passive"))
      (node (ref "J6") (pin "11") (pinfunction "11_11") (pintype "passive"))
      (node (ref "U6") (pin "16") (pinfunction "TXP_16") (pintype "passive"))
    )
    (net (code "64") (name "/MCO1") (class "Default")
      (node (ref "U1") (pin "100") (pinfunction "PA8_100") (pintype "passive"))
    )
    (net (code "65") (name "/Noise1A") (class "Default")
      (node (ref "C12") (pin "1") (pintype "passive"))
      (node (ref "J8") (pin "1") (pinfunction "1_1") (pintype "passive"))
      (node (ref "R19") (pin "1") (pinfunction "1_1") (pintype "passive"))
    )
    (net (code "66") (name "/Noise1B") (class "Default")
      (node (ref "C14") (pin "1") (pintype "passive"))
      (node (ref "J8") (pin "2") (pinfunction "2_2") (pintype "passive"))
      (node (ref "R33") (pin "2") (pinfunction "2_2") (pintype "passive"))
    )
    (net (code "67") (name "/Noise1_CPU") (class "Default")
      (node (ref "O4") (pin "4") (pinfunction "C_4") (pintype "passive"))
      (node (ref "R10") (pin "2") (pinfunction "2_2") (pintype "passive"))
      (node (ref "U1") (pin "41") (pinfunction "PA5_41") (pintype "passive"))
    )
    (net (code "68") (name "/Noise1_CPU_ADC") (class "Default")
      (node (ref "C10") (pin "1") (pintype "passive"))
      (node (ref "R7") (pin "1") (pinfunction "1_1") (pintype "passive"))
      (node (ref "R9") (pin "1") (pinfunction "1_1") (pintype "passive"))
      (node (ref "U1") (pin "13") (pinfunction "PF3_13") (pintype "passive"))
    )
    (net (code "69") (name "/Noise2A") (class "Default")
      (node (ref "C2") (pin "1") (pintype "passive"))
      (node (ref "J8") (pin "3") (pinfunction "3_3") (pintype "passive"))
      (node (ref "R3") (pin "1") (pinfunction "1_1") (pintype "passive"))
    )
    (net (code "70") (name "/Noise2B") (class "Default")
      (node (ref "C6") (pin "1") (pintype "passive"))
      (node (ref "J8") (pin "4") (pinfunction "4_4") (pintype "passive"))
      (node (ref "R11") (pin "2") (pinfunction "2_2") (pintype "passive"))
    )
    (net (code "71") (name "/Noise2_CPU") (class "Default")
      (node (ref "O5") (pin "4") (pinfunction "C_4") (pintype "passive"))
      (node (ref "R32") (pin "2") (pinfunction "2_2") (pintype "passive"))
      (node (ref "U1") (pin "37") (pinfunction "PA3_37") (pintype "passive"))
    )
    (net (code "72") (name "/Noise2_CPU_ADC") (class "Default")
      (node (ref "C19") (pin "1") (pintype "passive"))
      (node (ref "R24") (pin "1") (pinfunction "1_1") (pintype "passive"))
      (node (ref "R25") (pin "1") (pinfunction "1_1") (pintype "passive"))
      (node (ref "U1") (pin "14") (pinfunction "PF4_14") (pintype "passive"))
    )
    (net (code "73") (name "/OSCIN") (class "Default")
      (node (ref "C27") (pin "1") (pinfunction "1_1") (pintype "passive"))
      (node (ref "U1") (pin "23") (pinfunction "PH0-OSC_IN_23") (pintype "passive"))
      (node (ref "X1") (pin "2") (pinfunction "2_2") (pintype "passive"))
    )
    (net (code "74") (name "/OSCOUT") (class "Default")
      (node (ref "C29") (pin "1") (pinfunction "1_1") (pintype "passive"))
      (node (ref "U1") (pin "24") (pinfunction "PH1-OSC_OUT_24") (pintype "passive"))
      (node (ref "X1") (pin "1") (pinfunction "1_1") (pintype "passive"))
    )
    (net (code "75") (name "/OUT1") (class "Default")
      (node (ref "C64") (pin "2") (pintype "passive"))
      (node (ref "J5") (pin "10") (pinfunction "10_10") (pintype "passive"))
    )
    (net (code "76") (name "/OVP_CPU") (class "Default")
      (node (ref "J6") (pin "3") (pinfunction "3_3") (pintype "passive"))
      (node (ref "U1") (pin "50") (pinfunction "PF12_50") (pintype "passive"))
    )
    (net (code "77") (name "/PFB") (class "Default")
      (node (ref "C15") (pin "1") (pinfunction "1_1") (pintype "passive"))
      (node (ref "C16") (pin "2") (pinfunction "2_2") (pintype "passive"))
      (node (ref "C17") (pin "2") (pinfunction "2_2") (pintype "passive"))
      (node (ref "C18") (pin "2") (pinfunction "2_2") (pintype "passive"))
      (node (ref "IC2") (pin "18") (pinfunction "PFBIN1_18") (pintype "passive"))
      (node (ref "IC2") (pin "23") (pinfunction "PFBOUT_23") (pintype "passive"))
      (node (ref "IC2") (pin "37") (pinfunction "PFBIN2_37") (pintype "passive"))
    )
    (net (code "78") (name "/RD_N") (class "Default")
      (node (ref "IC2") (pin "13") (pinfunction "RD-_13") (pintype "passive"))
      (node (ref "R47") (pin "2") (pinfunction "2_2") (pintype "passive"))
      (node (ref "U6") (pin "8") (pinfunction "RDN_8") (pintype "passive"))
      (node (ref "U8") (pin "2") (pinfunction "2_2") (pintype "passive"))
    )
    (net (code "79") (name "/RD_P") (class "Default")
      (node (ref "IC2") (pin "14") (pinfunction "RD+_14") (pintype "passive"))
      (node (ref "R46") (pin "2") (pinfunction "2_2") (pintype "passive"))
      (node (ref "U6") (pin "6") (pinfunction "RDP_6") (pintype "passive"))
      (node (ref "U8") (pin "3") (pinfunction "3_3") (pintype "passive"))
    )
    (net (code "81") (name "/RST") (class "Default")
      (node (ref "C1") (pin "2") (pinfunction "2_2") (pintype "passive"))
      (node (ref "IC2") (pin "29") (pinfunction "RST_N_29") (pintype "passive"))
      (node (ref "U1") (pin "25") (pinfunction "NRST_25") (pintype "passive"))
      (node (ref "U3") (pin "4") (pinfunction "Y_4") (pintype "output"))
    )
    (net (code "82") (name "/Run_LED_CPU") (class "Default")
      (node (ref "R59") (pin "1") (pinfunction "1_1") (pintype "passive"))
      (node (ref "U1") (pin "63") (pinfunction "PE10_63") (pintype "passive"))
    )
    (net (code "83") (name "/Short_CPU") (class "Default")
      (node (ref "J6") (pin "4") (pinfunction "4_4") (pintype "passive"))
      (node (ref "R38") (pin "2") (pinfunction "2_2") (pintype "passive"))
      (node (ref "U1") (pin "49") (pinfunction "PF11_49") (pintype "passive"))
    )
    (net (code "84") (name "/TD_N") (class "Default")
      (node (ref "IC2") (pin "16") (pinfunction "TD-_16") (pintype "passive"))
      (node (ref "R45") (pin "2") (pinfunction "2_2") (pintype "passive"))
      (node (ref "U4") (pin "2") (pinfunction "2_2") (pintype "passive"))
      (node (ref "U6") (pin "3") (pinfunction "TDN_3") (pintype "passive"))
    )
    (net (code "85") (name "/TD_P") (class "Default")
      (node (ref "IC2") (pin "17") (pinfunction "TD+_17") (pintype "passive"))
      (node (ref "R44") (pin "2") (pinfunction "2_2") (pintype "passive"))
      (node (ref "U4") (pin "3") (pinfunction "3_3") (pintype "passive"))
      (node (ref "U6") (pin "1") (pinfunction "TDP_1") (pintype "passive"))
    )
    (net (code "86") (name "/TM1CH3") (class "Default")
      (node (ref "U1") (pin "102") (pinfunction "PA10_102") (pintype "passive"))
    )
    (net (code "87") (name "/TM3CH4") (class "Default")
      (node (ref "U1") (pin "47") (pinfunction "PB1_47") (pintype "passive"))
    )
    (net (code "88") (name "/U1RX") (class "Default")
      (node (ref "U1") (pin "137") (pinfunction "PB7_137") (pintype "passive"))
    )
    (net (code "89") (name "/U1TX") (class "Default")
      (node (ref "U1") (pin "136") (pinfunction "PB6_136") (pintype "passive"))
    )
    (net (code "90") (name "/U2RX") (class "Default")
      (node (ref "U1") (pin "122") (pinfunction "PD6_122") (pintype "passive"))
    )
    (net (code "91") (name "/U2TX") (class "Default")
      (node (ref "U1") (pin "119") (pinfunction "PD5_119") (pintype "passive"))
    )
    (net (code "92") (name "/UVP_CPU") (class "Default")
      (node (ref "J6") (pin "2") (pinfunction "2_2") (pintype "passive"))
      (node (ref "U1") (pin "53") (pinfunction "PF13_53") (pintype "passive"))
    )
    (net (code "93") (name "/V_Sampling") (class "Default")
      (node (ref "J6") (pin "9") (pinfunction "9_9") (pintype "passive"))
      (node (ref "R37") (pin "1") (pinfunction "1_1") (pintype "passive"))
    )
    (net (code "94") (name "/V_Sampling_U") (class "Default")
      (node (ref "C23") (pin "2") (pinfunction "2_2") (pintype "passive"))
      (node (ref "C76") (pin "2") (pinfunction "2_2") (pintype "passive"))
      (node (ref "D13") (pin "K") (pinfunction "K_K") (pintype "passive"))
      (node (ref "R37") (pin "2") (pinfunction "2_2") (pintype "passive"))
    )
    (net (code "95") (name "/Vol_Down") (class "Default")
      (node (ref "U1") (pin "60") (pinfunction "PE9_60") (pintype "passive"))
    )
    (net (code "96") (name "/Vol_Up") (class "Default")
      (node (ref "U1") (pin "64") (pinfunction "PE11_64") (pintype "passive"))
    )
    (net (code "97") (name "3V3A") (class "Default")
      (node (ref "C68") (pin "1") (pinfunction "1_1") (pintype "passive"))
      (node (ref "C73") (pin "2") (pinfunction "2_2") (pintype "passive"))
      (node (ref "L6") (pin "1") (pinfunction "1_1") (pintype "passive"))
      (node (ref "U5") (pin "5") (pinfunction "VDDA_5") (pintype "passive"))
    )
    (net (code "98") (name "AGND1") (class "Default")
      (node (ref "C1") (pin "1") (pinfunction "1_1") (pintype "passive"))
      (node (ref "C11") (pin "1") (pinfunction "1_1") (pintype "passive"))
      (node (ref "C13") (pin "1") (pinfunction "1_1") (pintype "passive"))
      (node (ref "C15") (pin "2") (pinfunction "2_2") (pintype "passive"))
      (node (ref "C16") (pin "1") (pinfunction "1_1") (pintype "passive"))
      (node (ref "C17") (pin "1") (pinfunction "1_1") (pintype "passive"))
      (node (ref "C18") (pin "1") (pinfunction "1_1") (pintype "passive"))
      (node (ref "C20") (pin "1") (pinfunction "1_1") (pintype "passive"))
      (node (ref "C21") (pin "2") (pinfunction "2_2") (pintype "passive"))
      (node (ref "C22") (pin "1") (pinfunction "1_1") (pintype "passive"))
      (node (ref "C23") (pin "1") (pinfunction "1_1") (pintype "passive"))
      (node (ref "C24") (pin "1") (pinfunction "1_1") (pintype "passive"))
      (node (ref "C26") (pin "1") (pinfunction "1_1") (pintype "passive"))
      (node (ref "C27") (pin "2") (pinfunction "2_2") (pintype "passive"))
      (node (ref "C29") (pin "2") (pinfunction "2_2") (pintype "passive"))
      (node (ref "C3") (pin "1") (pinfunction "1_1") (pintype "passive"))
      (node (ref "C30") (pin "2") (pinfunction "2_2") (pintype "passive"))
      (node (ref "C31") (pin "1") (pintype "passive"))
      (node (ref "C34") (pin "1") (pintype "passive"))
      (node (ref "C35") (pin "2") (pinfunction "2_2") (pintype "passive"))
      (node (ref "C36") (pin "1") (pinfunction "1_1") (pintype "passive"))
      (node (ref "C37") (pin "1") (pinfunction "1_1") (pintype "passive"))
      (node (ref "C38") (pin "2") (pinfunction "2_2") (pintype "passive"))
      (node (ref "C39") (pin "1") (pintype "passive"))
      (node (ref "C40") (pin "1") (pintype "passive"))
      (node (ref "C41") (pin "1") (pintype "passive"))
      (node (ref "C42") (pin "1") (pintype "passive"))
      (node (ref "C43") (pin "1") (pintype "passive"))
      (node (ref "C44") (pin "1") (pintype "passive"))
      (node (ref "C45") (pin "2") (pinfunction "2_2") (pintype "passive"))
      (node (ref "C46") (pin "1") (pinfunction "1_1") (pintype "passive"))
      (node (ref "C47") (pin "1") (pintype "passive"))
      (node (ref "C48") (pin "1") (pintype "passive"))
      (node (ref "C49") (pin "1") (pintype "passive"))
      (node (ref "C5") (pin "2") (pinfunction "2_2") (pintype "passive"))
      (node (ref "C50") (pin "1") (pintype "passive"))
      (node (ref "C51") (pin "1") (pintype "passive"))
      (node (ref "C52") (pin "1") (pintype "passive"))
      (node (ref "C53") (pin "1") (pinfunction "1_1") (pintype "passive"))
      (node (ref "C56") (pin "2") (pinfunction "2_2") (pintype "passive"))
      (node (ref "C57") (pin "1") (pinfunction "1_1") (pintype "passive"))
      (node (ref "C58") (pin "1") (pinfunction "1_1") (pintype "passive"))
      (node (ref "C62") (pin "1") (pinfunction "1_1") (pintype "passive"))
      (node (ref "C63") (pin "2") (pinfunction "2_2") (pintype "passive"))
      (node (ref "C65") (pin "2") (pinfunction "2_2") (pintype "passive"))
      (node (ref "C66") (pin "2") (pinfunction "2_2") (pintype "passive"))
      (node (ref "C67") (pin "1") (pinfunction "1_1") (pintype "passive"))
      (node (ref "C68") (pin "2") (pinfunction "2_2") (pintype "passive"))
      (node (ref "C69") (pin "1") (pinfunction "1_1") (pintype "passive"))
      (node (ref "C7") (pin "2") (pinfunction "2_2") (pintype "passive"))
      (node (ref "C70") (pin "2") (pinfunction "2_2") (pintype "passive"))
      (node (ref "C71") (pin "2") (pinfunction "2_2") (pintype "passive"))
      (node (ref "C72") (pin "2") (pinfunction "2_2") (pintype "passive"))
      (node (ref "C73") (pin "1") (pinfunction "1_1") (pintype "passive"))
      (node (ref "C74") (pin "2") (pinfunction "2_2") (pintype "passive"))
      (node (ref "C77") (pin "2") (pinfunction "2_2") (pintype "passive"))
      (node (ref "C8") (pin "1") (pinfunction "1_1") (pintype "passive"))
      (node (ref "C80") (pin "2") (pinfunction "2_2") (pintype "passive"))
      (node (ref "C81") (pin "1") (pinfunction "1_1") (pintype "passive"))
      (node (ref "C9") (pin "2") (pinfunction "2_2") (pintype "passive"))
      (node (ref "D10") (pin "A") (pinfunction "A_A") (pintype "passive"))
      (node (ref "D13") (pin "A") (pinfunction "A_A") (pintype "passive"))
      (node (ref "IC2") (pin "15") (pinfunction "AGND_15") (pintype "passive"))
      (node (ref "IC2") (pin "19") (pinfunction "AGND_19") (pintype "passive"))
      (node (ref "IC2") (pin "35") (pinfunction "IOGND_35") (pintype "passive"))
      (node (ref "IC2") (pin "36") (pinfunction "DGND_36") (pintype "passive"))
      (node (ref "IC2") (pin "47") (pinfunction "IOGND_47") (pintype "passive"))
      (node (ref "J2") (pin "10") (pinfunction "10_10") (pintype "passive"))
      (node (ref "J2") (pin "12") (pinfunction "12_12") (pintype "passive"))
      (node (ref "J2") (pin "14") (pinfunction "14_14") (pintype "passive"))
      (node (ref "J2") (pin "16") (pinfunction "16_16") (pintype "passive"))
      (node (ref "J2") (pin "18") (pinfunction "18_18") (pintype "passive"))
      (node (ref "J2") (pin "20") (pinfunction "20_20") (pintype "passive"))
      (node (ref "J2") (pin "4") (pinfunction "4_4") (pintype "passive"))
      (node (ref "J2") (pin "6") (pinfunction "6_6") (pintype "passive"))
      (node (ref "J2") (pin "8") (pinfunction "8_8") (pintype "passive"))
      (node (ref "J5") (pin "11") (pinfunction "11_11") (pintype "passive"))
      (node (ref "J5") (pin "2") (pinfunction "2_2") (pintype "passive"))
      (node (ref "J6") (pin "1") (pinfunction "1_1") (pintype "passive"))
      (node (ref "J6") (pin "10") (pinfunction "10_10") (pintype "passive"))
      (node (ref "J6") (pin "8") (pinfunction "8_8") (pintype "passive"))
      (node (ref "O4") (pin "3") (pinfunction "E_3") (pintype "passive"))
      (node (ref "O5") (pin "3") (pinfunction "E_3") (pintype "passive"))
      (node (ref "O6") (pin "3") (pinfunction "E_3") (pintype "passive"))
      (node (ref "O7") (pin "3") (pinfunction "E_3") (pintype "passive"))
      (node (ref "O8") (pin "3") (pinfunction "E_3") (pintype "passive"))
      (node (ref "O9") (pin "3") (pinfunction "E_3") (pintype "passive"))
      (node (ref "Q1") (pin "2") (pinfunction "E_2") (pintype "passive"))
      (node (ref "R1") (pin "1") (pinfunction "1_1") (pintype "passive"))
      (node (ref "R105") (pin "1") (pinfunction "1_1") (pintype "passive"))
      (node (ref "R24") (pin "2") (pinfunction "2_2") (pintype "passive"))
      (node (ref "R29") (pin "1") (pinfunction "1_1") (pintype "passive"))
      (node (ref "R30") (pin "1") (pinfunction "1_1") (pintype "passive"))
      (node (ref "R31") (pin "1") (pinfunction "1_1") (pintype "passive"))
      (node (ref "R35") (pin "2") (pinfunction "2_2") (pintype "passive"))
      (node (ref "R40") (pin "2") (pinfunction "2_2") (pintype "passive"))
      (node (ref "R42") (pin "2") (pinfunction "2_2") (pintype "passive"))
      (node (ref "R50") (pin "1") (pinfunction "1_1") (pintype "passive"))
      (node (ref "R67") (pin "2") (pinfunction "2_2") (pintype "passive"))
      (node (ref "R76") (pin "1") (pinfunction "1_1") (pintype "passive"))
      (node (ref "R9") (pin "2") (pinfunction "2_2") (pintype "passive"))
      (node (ref "R97") (pin "1") (pinfunction "1_1") (pintype "passive"))
      (node (ref "S1") (pin "1") (pinfunction "1_1") (pintype "passive"))
      (node (ref "T4") (pin "5") (pinfunction "5_5") (pintype "passive"))
      (node (ref "T5") (pin "5") (pinfunction "5_5") (pintype "passive"))
      (node (ref "T6") (pin "1") (pintype "passive"))
      (node (ref "U1") (pin "107") (pinfunction "Vss_2_107") (pintype "passive"))
      (node (ref "U1") (pin "120") (pinfunction "Vss_10_120") (pintype "passive"))
      (node (ref "U1") (pin "130") (pinfunction "Vss_11_130") (pintype "passive"))
      (node (ref "U1") (pin "16") (pinfunction "Vss_5_16") (pintype "passive"))
      (node (ref "U1") (pin "31") (pinfunction "VssA_31") (pintype "passive"))
      (node (ref "U1") (pin "38") (pinfunction "Vss_4_38") (pintype "passive"))
      (node (ref "U1") (pin "51") (pinfunction "Vss_6_51") (pintype "passive"))
      (node (ref "U1") (pin "61") (pinfunction "Vss_7_61") (pintype "passive"))
      (node (ref "U1") (pin "83") (pinfunction "Vss_8_83") (pintype "passive"))
      (node (ref "U1") (pin "94") (pinfunction "Vss_9_94") (pintype "passive"))
      (node (ref "U10") (pin "4") (pinfunction "COM_4") (pintype "passive"))
      (node (ref "U12") (pin "1") (pinfunction "GND_1") (pintype "passive"))
      (node (ref "U2") (pin "3") (pinfunction "GND_3") (pintype "passive"))
      (node (ref "U3") (pin "3") (pinfunction "G_3") (pintype "passive"))
      (node (ref "U4") (pin "1") (pinfunction "1_1") (pintype "passive"))
      (node (ref "U5") (pin "1") (pinfunction "GND1_1") (pintype "passive"))
      (node (ref "U5") (pin "3") (pinfunction "GND2_3") (pintype "passive"))
      (node (ref "U5") (pin "31") (pinfunction "CTRL_ADR0_CS_31") (pintype "passive"))
      (node (ref "U5") (pin "32") (pinfunction "CTRL_MODE_32") (pintype "passive"))
      (node (ref "U5") (pin "33") (pinfunction "GND_PAD_33") (pintype "passive"))
      (node (ref "U5") (pin "34") (pinfunction "GND3_34") (pintype "passive"))
      (node (ref "U5") (pin "35") (pinfunction "GND4_35") (pintype "passive"))
      (node (ref "U5") (pin "36") (pinfunction "GND5_36") (pintype "passive"))
      (node (ref "U5") (pin "37") (pinfunction "GND6_37") (pintype "passive"))
      (node (ref "U5") (pin "7") (pinfunction "AGND_7") (pintype "passive"))
      (node (ref "U8") (pin "1") (pinfunction "1_1") (pintype "passive"))
      (node (ref "U9") (pin "1") (pinfunction "A0_1") (pintype "passive"))
      (node (ref "U9") (pin "2") (pinfunction "A1_2") (pintype "passive"))
      (node (ref "U9") (pin "3") (pinfunction "A2_3") (pintype "passive"))
      (node (ref "U9") (pin "4") (pinfunction "GND_4") (pintype "passive"))
      (node (ref "U9") (pin "7") (pinfunction "WP_7") (pintype "passive"))
      (node (ref "Y1") (pin "2") (pinfunction "GND_2") (pintype "passive"))
      (node (ref "Y2") (pin "2") (pinfunction "GND_2") (pintype "passive"))
    )
    (net (code "99") (name "DC+3.3V") (class "Default")
      (node (ref "C11") (pin "2") (pinfunction "2_2") (pintype "passive"))
      (node (ref "C20") (pin "2") (pinfunction "2_2") (pintype "passive"))
      (node (ref "C22") (pin "2") (pinfunction "2_2") (pintype "passive"))
      (node (ref "C24") (pin "2") (pinfunction "2_2") (pintype "passive"))
      (node (ref "C34") (pin "2") (pintype "passive"))
      (node (ref "C38") (pin "1") (pinfunction "1_1") (pintype "passive"))
      (node (ref "C39") (pin "2") (pintype "passive"))
      (node (ref "C40") (pin "2") (pintype "passive"))
      (node (ref "C41") (pin "2") (pintype "passive"))
      (node (ref "C42") (pin "2") (pintype "passive"))
      (node (ref "C43") (pin "2") (pintype "passive"))
      (node (ref "C44") (pin "2") (pintype "passive"))
      (node (ref "C47") (pin "2") (pintype "passive"))
      (node (ref "C48") (pin "2") (pintype "passive"))
      (node (ref "C49") (pin "2") (pintype "passive"))
      (node (ref "C50") (pin "2") (pintype "passive"))
      (node (ref "C51") (pin "2") (pintype "passive"))
      (node (ref "C52") (pin "2") (pintype "passive"))
      (node (ref "C53") (pin "2") (pinfunction "2_2") (pintype "passive"))
      (node (ref "C69") (pin "2") (pinfunction "2_2") (pintype "passive"))
      (node (ref "C7") (pin "1") (pinfunction "1_1") (pintype "passive"))
      (node (ref "C71") (pin "1") (pinfunction "1_1") (pintype "passive"))
      (node (ref "C74") (pin "1") (pinfunction "1_1") (pintype "passive"))
      (node (ref "C77") (pin "1") (pinfunction "1_1") (pintype "passive"))
      (node (ref "C8") (pin "2") (pinfunction "2_2") (pintype "passive"))
      (node (ref "C9") (pin "1") (pinfunction "1_1") (pintype "passive"))
      (node (ref "IC2") (pin "22") (pinfunction "AVDD33_22") (pintype "passive"))
      (node (ref "IC2") (pin "32") (pinfunction "IOVDD33_32") (pintype "passive"))
      (node (ref "IC2") (pin "48") (pinfunction "IOVDD33_48") (pintype "passive"))
      (node (ref "J2") (pin "1") (pinfunction "1_1") (pintype "passive"))
      (node (ref "J2") (pin "2") (pinfunction "2_2") (pintype "passive"))
      (node (ref "J5") (pin "1") (pinfunction "1_1") (pintype "passive"))
      (node (ref "L6") (pin "2") (pinfunction "2_2") (pintype "passive"))
      (node (ref "LED1") (pin "1") (pinfunction "1_1") (pintype "passive"))
      (node (ref "LED2") (pin "1") (pinfunction "1_1") (pintype "passive"))
      (node (ref "O10") (pin "4") (pinfunction "C_4") (pintype "passive"))
      (node (ref "R10") (pin "1") (pinfunction "1_1") (pintype "passive"))
      (node (ref "R12") (pin "2") (pinfunction "2_2") (pintype "passive"))
      (node (ref "R13") (pin "1") (pinfunction "1_1") (pintype "passive"))
      (node (ref "R14") (pin "2") (pinfunction "2_2") (pintype "passive"))
      (node (ref "R15") (pin "2") (pinfunction "2_2") (pintype "passive"))
      (node (ref "R18") (pin "1") (pinfunction "1_1") (pintype "passive"))
      (node (ref "R2") (pin "1") (pinfunction "1_1") (pintype "passive"))
      (node (ref "R21") (pin "2") (pinfunction "2_2") (pintype "passive"))
      (node (ref "R25") (pin "2") (pinfunction "2_2") (pintype "passive"))
      (node (ref "R26") (pin "1") (pinfunction "1_1") (pintype "passive"))
      (node (ref "R26") (pin "2") (pinfunction "2_2") (pintype "passive"))
      (node (ref "R26") (pin "3") (pinfunction "3_3") (pintype "passive"))
      (node (ref "R26") (pin "4") (pinfunction "4_4") (pintype "passive"))
      (node (ref "R32") (pin "1") (pinfunction "1_1") (pintype "passive"))
      (node (ref "R34") (pin "2") (pinfunction "2_2") (pintype "passive"))
      (node (ref "R36") (pin "2") (pinfunction "2_2") (pintype "passive"))
      (node (ref "R38") (pin "1") (pinfunction "1_1") (pintype "passive"))
      (node (ref "R43") (pin "2") (pinfunction "2_2") (pintype "passive"))
      (node (ref "R44") (pin "1") (pinfunction "1_1") (pintype "passive"))
      (node (ref "R45") (pin "1") (pinfunction "1_1") (pintype "passive"))
      (node (ref "R46") (pin "1") (pinfunction "1_1") (pintype "passive"))
      (node (ref "R47") (pin "1") (pinfunction "1_1") (pintype "passive"))
      (node (ref "R48") (pin "1") (pinfunction "1_1") (pintype "passive"))
      (node (ref "R55") (pin "1") (pinfunction "1_1") (pintype "passive"))
      (node (ref "R56") (pin "1") (pinfunction "1_1") (pintype "passive"))
      (node (ref "R60") (pin "1") (pinfunction "1_1") (pintype "passive"))
      (node (ref "R61") (pin "1") (pinfunction "1_1") (pintype "passive"))
      (node (ref "R62") (pin "1") (pinfunction "1_1") (pintype "passive"))
      (node (ref "R65") (pin "1") (pinfunction "1_1") (pintype "passive"))
      (node (ref "R66") (pin "1") (pinfunction "1_1") (pintype "passive"))
      (node (ref "R7") (pin "2") (pinfunction "2_2") (pintype "passive"))
      (node (ref "R8") (pin "1") (pinfunction "1_1") (pintype "passive"))
      (node (ref "U1") (pin "108") (pinfunction "Vdd_2_108") (pintype "passive"))
      (node (ref "U1") (pin "121") (pinfunction "Vdd_10_121") (pintype "passive"))
      (node (ref "U1") (pin "131") (pinfunction "Vdd_11_131") (pintype "passive"))
      (node (ref "U1") (pin "144") (pinfunction "Vdd_3_144") (pintype "passive"))
      (node (ref "U1") (pin "17") (pinfunction "Vdd_5_17") (pintype "passive"))
      (node (ref "U1") (pin "30") (pinfunction "Vdd_12_30") (pintype "passive"))
      (node (ref "U1") (pin "33") (pinfunction "VddA_33") (pintype "passive"))
      (node (ref "U1") (pin "39") (pinfunction "Vdd_4_39") (pintype "passive"))
      (node (ref "U1") (pin "52") (pinfunction "Vdd_6_52") (pintype "passive"))
      (node (ref "U1") (pin "6") (pinfunction "Vbat_6") (pintype "passive"))
      (node (ref "U1") (pin "62") (pinfunction "Vdd_7_62") (pintype "passive"))
      (node (ref "U1") (pin "72") (pinfunction "Vdd_1_72") (pintype "passive"))
      (node (ref "U1") (pin "84") (pinfunction "Vdd_8_84") (pintype "passive"))
      (node (ref "U1") (pin "95") (pinfunction "Vdd_9_95") (pintype "passive"))
      (node (ref "U12") (pin "2") (pinfunction "Vout_2") (pintype "passive"))
      (node (ref "U12") (pin "4") (pinfunction "Vout_4") (pintype "passive"))
      (node (ref "U2") (pin "2") (pinfunction "VCC_2") (pintype "passive"))
      (node (ref "U3") (pin "5") (pinfunction "V_5") (pintype "passive"))
      (node (ref "U5") (pin "20") (pinfunction "VDDIO_20") (pintype "passive"))
      (node (ref "U9") (pin "8") (pinfunction "VCC_8") (pintype "passive"))
      (node (ref "Y1") (pin "4") (pinfunction "VCC_4") (pintype "passive"))
      (node (ref "Y2") (pin "4") (pinfunction "VCC_4") (pintype "passive"))
    )
    (net (code "100") (name "DC+5V") (class "Default")
      (node (ref "C56") (pin "1") (pinfunction "1_1") (pintype "passive"))
      (node (ref "C58") (pin "2") (pinfunction "2_2") (pintype "passive"))
      (node (ref "C70") (pin "1") (pinfunction "1_1") (pintype "passive"))
      (node (ref "C72") (pin "1") (pinfunction "1_1") (pintype "passive"))
      (node (ref "D4") (pin "K") (pinfunction "K_K") (pintype "passive"))
      (node (ref "R68") (pin "2") (pinfunction "2_2") (pintype "passive"))
      (node (ref "Re1") (pin "1") (pintype "passive"))
      (node (ref "U10") (pin "5") (pinfunction "OUT+_5") (pintype "passive"))
      (node (ref "U12") (pin "3") (pinfunction "Vin_3") (pintype "passive"))
    )
    (net (code "101") (name "DC+24V") (class "Default")
      (node (ref "J6") (pin "5") (pinfunction "5_5") (pintype "passive"))
      (node (ref "R19") (pin "2") (pinfunction "2_2") (pintype "passive"))
      (node (ref "R3") (pin "2") (pinfunction "2_2") (pintype "passive"))
      (node (ref "R57") (pin "2") (pinfunction "2_2") (pintype "passive"))
      (node (ref "R58") (pin "2") (pinfunction "2_2") (pintype "passive"))
      (node (ref "R63") (pin "2") (pinfunction "2_2") (pintype "passive"))
      (node (ref "R64") (pin "2") (pinfunction "2_2") (pintype "passive"))
    )
    (net (code "102") (name "DC-5V") (class "Default")
      (node (ref "C62") (pin "2") (pinfunction "2_2") (pintype "passive"))
      (node (ref "C63") (pin "1") (pinfunction "1_1") (pintype "passive"))
      (node (ref "R80") (pin "2") (pinfunction "2_2") (pintype "passive"))
      (node (ref "U10") (pin "3") (pinfunction "OUT-_3") (pintype "passive"))
    )
    (net (code "103") (name "DC110V") (class "Default")
      (node (ref "D3") (pin "A") (pinfunction "1_A") (pintype "passive"))
      (node (ref "J4") (pin "2") (pinfunction "2_2") (pintype "passive"))
      (node (ref "R98") (pin "2") (pinfunction "2_2") (pintype "passive"))
    )
    (net (code "104") (name "DC110VGND") (class "Default")
      (node (ref "C59") (pin "2") (pinfunction "2_2") (pintype "passive"))
      (node (ref "C60") (pin "1") (pinfunction "1_1") (pintype "passive"))
      (node (ref "J4") (pin "1") (pinfunction "1_1") (pintype "passive"))
      (node (ref "U10") (pin "2") (pinfunction "IN-_2") (pintype "passive"))
    )
    (net (code "105") (name "EARTH") (class "Default")
      (node (ref "C33") (pin "1") (pinfunction "1_1") (pintype "passive"))
      (node (ref "C35") (pin "1") (pinfunction "1_1") (pintype "passive"))
    )
    (net (code "106") (name "Net-(C2-Pad2)") (class "Default")
      (node (ref "C2") (pin "2") (pintype "passive"))
      (node (ref "T4") (pin "2") (pinfunction "2_2") (pintype "passive"))
    )
    (net (code "107") (name "Net-(C6-Pad2)") (class "Default")
      (node (ref "C6") (pin "2") (pintype "passive"))
      (node (ref "T4") (pin "1") (pinfunction "1_1") (pintype "passive"))
    )
    (net (code "108") (name "Net-(C10-Pad2)") (class "Default")
      (node (ref "C10") (pin "2") (pintype "passive"))
      (node (ref "C3") (pin "2") (pinfunction "2_2") (pintype "passive"))
      (node (ref "R5") (pin "2") (pinfunction "2_2") (pintype "passive"))
    )
    (net (code "109") (name "Net-(C12-Pad2)") (class "Default")
      (node (ref "C12") (pin "2") (pintype "passive"))
      (node (ref "T5") (pin "2") (pinfunction "2_2") (pintype "passive"))
    )
    (net (code "110") (name "Net-(C13-Pad2)") (class "Default")
      (node (ref "C13") (pin "2") (pinfunction "2_2") (pintype "passive"))
      (node (ref "C19") (pin "2") (pintype "passive"))
      (node (ref "R23") (pin "2") (pinfunction "2_2") (pintype "passive"))
    )
    (net (code "111") (name "Net-(C14-Pad2)") (class "Default")
      (node (ref "C14") (pin "2") (pintype "passive"))
      (node (ref "T5") (pin "1") (pinfunction "1_1") (pintype "passive"))
    )
    (net (code "112") (name "Net-(C33-Pad2)") (class "Default")
      (node (ref "C33") (pin "2") (pinfunction "2_2") (pintype "passive"))
      (node (ref "R53") (pin "2") (pinfunction "2_2") (pintype "passive"))
      (node (ref "R54") (pin "2") (pinfunction "2_2") (pintype "passive"))
    )
    (net (code "113") (name "Net-(C54-Pad1)") (class "Default")
      (node (ref "C54") (pin "1") (pinfunction "1_1") (pintype "passive"))
      (node (ref "IC4") (pin "2") (pintype "passive"))
      (node (ref "R70") (pin "2") (pinfunction "2_2") (pintype "passive"))
      (node (ref "R71") (pin "1") (pinfunction "1_1") (pintype "passive"))
      (node (ref "R74") (pin "2") (pinfunction "2_2") (pintype "passive"))
      (node (ref "R75") (pin "1") (pinfunction "1_1") (pintype "passive"))
    )
    (net (code "114") (name "Net-(C54-Pad2)") (class "Default")
      (node (ref "C54") (pin "2") (pinfunction "2_2") (pintype "passive"))
      (node (ref "C64") (pin "1") (pintype "passive"))
      (node (ref "IC4") (pin "1") (pintype "passive"))
      (node (ref "R71") (pin "2") (pinfunction "2_2") (pintype "passive"))
    )
    (net (code "115") (name "Net-(C55-Pad1)") (class "Default")
      (node (ref "C55") (pin "1") (pinfunction "1_1") (pintype "passive"))
      (node (ref "R70") (pin "1") (pinfunction "1_1") (pintype "passive"))
    )
    (net (code "116") (name "Net-(C57-Pad2)") (class "Default")
      (node (ref "C57") (pin "2") (pinfunction "2_2") (pintype "passive"))
      (node (ref "IC4") (pin "8") (pintype "passive"))
      (node (ref "R68") (pin "1") (pinfunction "1_1") (pintype "passive"))
    )
    (net (code "117") (name "Net-(C61-Pad1)") (class "Default")
      (node (ref "C61") (pin "1") (pinfunction "1_1") (pintype "passive"))
      (node (ref "R74") (pin "1") (pinfunction "1_1") (pintype "passive"))
    )
    (net (code "118") (name "Net-(C67-Pad2)") (class "Default")
      (node (ref "C67") (pin "2") (pinfunction "2_2") (pintype "passive"))
      (node (ref "IC4") (pin "4") (pintype "passive"))
      (node (ref "R80") (pin "1") (pinfunction "1_1") (pintype "passive"))
    )
    (net (code "119") (name "Net-(C78-Pad1)") (class "Default")
      (node (ref "C78") (pin "1") (pinfunction "1_1") (pintype "passive"))
      (node (ref "IC4") (pin "6") (pintype "passive"))
      (node (ref "R103") (pin "2") (pinfunction "2_2") (pintype "passive"))
      (node (ref "R99") (pin "1") (pinfunction "1_1") (pintype "passive"))
    )
    (net (code "120") (name "Net-(C78-Pad2)") (class "Default")
      (node (ref "C78") (pin "2") (pinfunction "2_2") (pintype "passive"))
      (node (ref "C82") (pin "2") (pinfunction "2_2") (pintype "passive"))
      (node (ref "IC4") (pin "7") (pintype "passive"))
      (node (ref "R99") (pin "2") (pinfunction "2_2") (pintype "passive"))
    )
    (net (code "121") (name "Net-(C80-Pad1)") (class "Default")
      (node (ref "C80") (pin "1") (pinfunction "1_1") (pintype "passive"))
      (node (ref "R103") (pin "1") (pinfunction "1_1") (pintype "passive"))
      (node (ref "T6") (pin "2") (pintype "passive"))
    )
    (net (code "122") (name "Net-(C82-Pad1)") (class "Default")
      (node (ref "C82") (pin "1") (pinfunction "1_1") (pintype "passive"))
      (node (ref "R50") (pin "2") (pinfunction "2_2") (pintype "passive"))
      (node (ref "Re1") (pin "5") (pintype "passive"))
    )
    (net (code "123") (name "Net-(C83-Pad1)") (class "Default")
      (node (ref "C83") (pin "1") (pinfunction "1_1") (pintype "passive"))
      (node (ref "R75") (pin "2") (pinfunction "2_2") (pintype "passive"))
    )
    (net (code "124") (name "Net-(C83-Pad2)") (class "Default")
      (node (ref "C83") (pin "2") (pinfunction "2_2") (pintype "passive"))
      (node (ref "R67") (pin "1") (pinfunction "1_1") (pintype "passive"))
      (node (ref "Re1") (pin "6") (pintype "passive"))
    )
    (net (code "125") (name "Net-(D1-1)") (class "Default")
      (node (ref "D1") (pin "A") (pinfunction "1_A") (pintype "passive"))
      (node (ref "O4") (pin "2") (pinfunction "K_2") (pintype "passive"))
    )
    (net (code "126") (name "Net-(D2-1)") (class "Default")
      (node (ref "D2") (pin "A") (pinfunction "1_A") (pintype "passive"))
      (node (ref "O5") (pin "2") (pinfunction "K_2") (pintype "passive"))
    )
    (net (code "127") (name "Net-(D3-2)") (class "Default")
      (node (ref "C59") (pin "1") (pinfunction "1_1") (pintype "passive"))
      (node (ref "C60") (pin "2") (pinfunction "2_2") (pintype "passive"))
      (node (ref "D3") (pin "K") (pinfunction "2_K") (pintype "passive"))
      (node (ref "U10") (pin "1") (pinfunction "IN+_1") (pintype "passive"))
    )
    (net (code "128") (name "Net-(D7-PadA)") (class "Default")
      (node (ref "D7") (pin "A") (pintype "passive"))
      (node (ref "JP1") (pin "2") (pintype "passive"))
    )
    (net (code "129") (name "Net-(D14-1)") (class "Default")
      (node (ref "D14") (pin "A") (pinfunction "1_A") (pintype "passive"))
      (node (ref "O6") (pin "2") (pinfunction "K_2") (pintype "passive"))
    )
    (net (code "130") (name "Net-(D15-1)") (class "Default")
      (node (ref "D15") (pin "A") (pinfunction "1_A") (pintype "passive"))
      (node (ref "O7") (pin "2") (pinfunction "K_2") (pintype "passive"))
    )
    (net (code "131") (name "Net-(D16-1)") (class "Default")
      (node (ref "D16") (pin "A") (pinfunction "1_A") (pintype "passive"))
      (node (ref "O8") (pin "2") (pinfunction "K_2") (pintype "passive"))
    )
    (net (code "132") (name "Net-(D17-1)") (class "Default")
      (node (ref "D17") (pin "A") (pinfunction "1_A") (pintype "passive"))
      (node (ref "O9") (pin "2") (pinfunction "K_2") (pintype "passive"))
    )
    (net (code "133") (name "Net-(D19-1)") (class "Default")
      (node (ref "D19") (pin "A") (pinfunction "1_A") (pintype "passive"))
      (node (ref "O10") (pin "2") (pinfunction "K_2") (pintype "passive"))
    )
    (net (code "134") (name "Net-(D19-2)") (class "Default")
      (node (ref "D19") (pin "K") (pinfunction "2_K") (pintype "passive"))
      (node (ref "T6") (pin "4") (pintype "passive"))
    )
    (net (code "135") (name "Net-(IC2-CRS)") (class "Default")
      (node (ref "IC2") (pin "40") (pinfunction "CRS_40") (pintype "passive"))
      (node (ref "R4") (pin "4") (pinfunction "4_4") (pintype "passive"))
    )
    (net (code "136") (name "Net-(IC2-MDC)") (class "Default")
      (node (ref "IC2") (pin "31") (pinfunction "MDC_31") (pintype "passive"))
      (node (ref "R20") (pin "1") (pinfunction "1_1") (pintype "passive"))
    )
    (net (code "137") (name "Net-(IC2-MDIO)") (class "Default")
      (node (ref "IC2") (pin "30") (pinfunction "MDIO_30") (pintype "passive"))
      (node (ref "R18") (pin "2") (pinfunction "2_2") (pintype "passive"))
      (node (ref "R22") (pin "1") (pinfunction "1_1") (pintype "passive"))
    )
    (net (code "138") (name "Net-(IC2-PWR_DOWN{slash}INT)") (class "Default")
      (node (ref "IC2") (pin "7") (pinfunction "PWR_DOWN/INT_7") (pintype "passive"))
      (node (ref "R21") (pin "1") (pinfunction "1_1") (pintype "passive"))
    )
    (net (code "139") (name "Net-(IC2-RBIAS)") (class "Default")
      (node (ref "IC2") (pin "24") (pinfunction "RBIAS_24") (pintype "passive"))
      (node (ref "R35") (pin "1") (pinfunction "1_1") (pintype "passive"))
    )
    (net (code "140") (name "Net-(IC2-RESERVED-Pad20)") (class "Default")
      (node (ref "IC2") (pin "20") (pinfunction "RESERVED_20") (pintype "passive"))
      (node (ref "R34") (pin "1") (pinfunction "1_1") (pintype "passive"))
    )
    (net (code "141") (name "Net-(IC2-RESERVED-Pad21)") (class "Default")
      (node (ref "IC2") (pin "21") (pinfunction "RESERVED_21") (pintype "passive"))
      (node (ref "R36") (pin "1") (pinfunction "1_1") (pintype "passive"))
    )
    (net (code "142") (name "Net-(IC2-RXD_0)") (class "Default")
      (node (ref "IC2") (pin "43") (pinfunction "RXD_0_43") (pintype "passive"))
      (node (ref "R4") (pin "2") (pinfunction "2_2") (pintype "passive"))
    )
    (net (code "143") (name "Net-(IC2-RXD_1)") (class "Default")
      (node (ref "IC2") (pin "44") (pinfunction "RXD_1_44") (pintype "passive"))
      (node (ref "R4") (pin "1") (pinfunction "1_1") (pintype "passive"))
    )
    (net (code "144") (name "Net-(IC2-RX_DV)") (class "Default")
      (node (ref "IC2") (pin "39") (pinfunction "RX_DV_39") (pintype "passive"))
      (node (ref "R8") (pin "2") (pinfunction "2_2") (pintype "passive"))
    )
    (net (code "145") (name "Net-(IC2-RX_ER)") (class "Default")
      (node (ref "IC2") (pin "41") (pinfunction "RX_ER_41") (pintype "passive"))
      (node (ref "R4") (pin "3") (pinfunction "3_3") (pintype "passive"))
    )
    (net (code "146") (name "Net-(IC2-TXD_0)") (class "Default")
      (node (ref "IC2") (pin "3") (pinfunction "TXD_0_3") (pintype "passive"))
      (node (ref "R17") (pin "2") (pinfunction "2_2") (pintype "passive"))
    )
    (net (code "147") (name "Net-(IC2-TXD_1)") (class "Default")
      (node (ref "IC2") (pin "4") (pinfunction "TXD_1_4") (pintype "passive"))
      (node (ref "R17") (pin "1") (pinfunction "1_1") (pintype "passive"))
    )
    (net (code "148") (name "Net-(IC2-TX_EN)") (class "Default")
      (node (ref "IC2") (pin "2") (pinfunction "TX_EN_2") (pintype "passive"))
      (node (ref "R17") (pin "3") (pinfunction "3_3") (pintype "passive"))
    )
    (net (code "149") (name "Net-(IC4-Pad3)") (class "Default")
      (node (ref "IC4") (pin "3") (pintype "passive"))
      (node (ref "R76") (pin "2") (pinfunction "2_2") (pintype "passive"))
    )
    (net (code "150") (name "Net-(IC4-Pad5)") (class "Default")
      (node (ref "IC4") (pin "5") (pintype "passive"))
      (node (ref "R105") (pin "2") (pinfunction "2_2") (pintype "passive"))
    )
    (net (code "151") (name "Net-(J2-Pad11)") (class "Default")
      (node (ref "J2") (pin "11") (pinfunction "11_11") (pintype "passive"))
      (node (ref "R30") (pin "2") (pinfunction "2_2") (pintype "passive"))
    )
    (net (code "152") (name "Net-(J2-Pad17)") (class "Default")
      (node (ref "J2") (pin "17") (pinfunction "17_17") (pintype "passive"))
      (node (ref "R31") (pin "2") (pinfunction "2_2") (pintype "passive"))
    )
    (net (code "153") (name "Net-(LED1-Pad2)") (class "Default")
      (node (ref "LED1") (pin "2") (pinfunction "2_2") (pintype "passive"))
      (node (ref "R59") (pin "2") (pinfunction "2_2") (pintype "passive"))
    )
    (net (code "154") (name "Net-(LED2-Pad2)") (class "Default")
      (node (ref "LED2") (pin "2") (pinfunction "2_2") (pintype "passive"))
      (node (ref "R1") (pin "2") (pinfunction "2_2") (pintype "passive"))
    )
    (net (code "155") (name "Net-(O4-A)") (class "Default")
      (node (ref "O4") (pin "1") (pinfunction "A_1") (pintype "passive"))
      (node (ref "R11") (pin "1") (pinfunction "1_1") (pintype "passive"))
    )
    (net (code "156") (name "Net-(O5-A)") (class "Default")
      (node (ref "O5") (pin "1") (pinfunction "A_1") (pintype "passive"))
      (node (ref "R33") (pin "1") (pinfunction "1_1") (pintype "passive"))
    )
    (net (code "157") (name "Net-(O6-A)") (class "Default")
      (node (ref "O6") (pin "1") (pinfunction "A_1") (pintype "passive"))
      (node (ref "R57") (pin "1") (pinfunction "1_1") (pintype "passive"))
    )
    (net (code "158") (name "Net-(O7-A)") (class "Default")
      (node (ref "O7") (pin "1") (pinfunction "A_1") (pintype "passive"))
      (node (ref "R58") (pin "1") (pinfunction "1_1") (pintype "passive"))
    )
    (net (code "159") (name "Net-(O8-A)") (class "Default")
      (node (ref "O8") (pin "1") (pinfunction "A_1") (pintype "passive"))
      (node (ref "R63") (pin "1") (pinfunction "1_1") (pintype "passive"))
    )
    (net (code "160") (name "Net-(O9-A)") (class "Default")
      (node (ref "O9") (pin "1") (pinfunction "A_1") (pintype "passive"))
      (node (ref "R64") (pin "1") (pinfunction "1_1") (pintype "passive"))
    )
    (net (code "161") (name "Net-(O10-A)") (class "Default")
      (node (ref "O10") (pin "1") (pinfunction "A_1") (pintype "passive"))
      (node (ref "R98") (pin "1") (pinfunction "1_1") (pintype "passive"))
    )
    (net (code "162") (name "Net-(Q1-B)") (class "Default")
      (node (ref "Q1") (pin "1") (pinfunction "B_1") (pintype "passive"))
      (node (ref "R6") (pin "2") (pinfunction "2_2") (pintype "passive"))
    )
    (net (code "163") (name "Net-(Q1-C)") (class "Default")
      (node (ref "D4") (pin "A") (pinfunction "A_A") (pintype "passive"))
      (node (ref "Q1") (pin "3") (pinfunction "C_3") (pintype "passive"))
      (node (ref "Re1") (pin "8") (pintype "passive"))
    )
    (net (code "164") (name "Net-(R5-Pad1)") (class "Default")
      (node (ref "R5") (pin "1") (pinfunction "1_1") (pintype "passive"))
      (node (ref "T4") (pin "3") (pinfunction "3_3") (pintype "passive"))
    )
    (net (code "165") (name "Net-(R23-Pad1)") (class "Default")
      (node (ref "R23") (pin "1") (pinfunction "1_1") (pintype "passive"))
      (node (ref "T5") (pin "3") (pinfunction "3_3") (pintype "passive"))
    )
    (net (code "166") (name "Net-(U1-VCAP_1)") (class "Default")
      (node (ref "C37") (pin "2") (pinfunction "2_2") (pintype "passive"))
      (node (ref "U1") (pin "71") (pinfunction "VCAP_1_71") (pintype "passive"))
    )
    (net (code "167") (name "Net-(U1-VCAP_2)") (class "Default")
      (node (ref "C36") (pin "2") (pinfunction "2_2") (pintype "passive"))
      (node (ref "U1") (pin "106") (pinfunction "VCAP_2_106") (pintype "passive"))
    )
    (net (code "168") (name "Net-(U1-Vref+)") (class "Default")
      (node (ref "C45") (pin "1") (pinfunction "1_1") (pintype "passive"))
      (node (ref "C46") (pin "2") (pinfunction "2_2") (pintype "passive"))
      (node (ref "R60") (pin "2") (pinfunction "2_2") (pintype "passive"))
      (node (ref "U1") (pin "32") (pinfunction "Vref+_32") (pintype "passive"))
    )
    (net (code "169") (name "Net-(U2-MR)") (class "Default")
      (node (ref "C21") (pin "1") (pinfunction "1_1") (pintype "passive"))
      (node (ref "JP1") (pin "1") (pintype "passive"))
      (node (ref "S1") (pin "2") (pinfunction "2_2") (pintype "passive"))
      (node (ref "U2") (pin "1") (pinfunction "MR_1") (pintype "passive"))
    )
    (net (code "170") (name "Net-(U2-RESET)") (class "Default")
      (node (ref "R43") (pin "1") (pinfunction "1_1") (pintype "passive"))
      (node (ref "U2") (pin "7") (pinfunction "RESET_7") (pintype "passive"))
      (node (ref "U3") (pin "1") (pinfunction "A_1") (pintype "input"))
    )
    (net (code "171") (name "Net-(U2-WDO)") (class "Default")
      (node (ref "D7") (pin "K") (pintype "passive"))
      (node (ref "U2") (pin "8") (pinfunction "WDO_8") (pintype "passive"))
    )
    (net (code "172") (name "Net-(U5-I2S_DIN)") (class "Default")
      (node (ref "R91") (pin "2") (pinfunction "2_2") (pintype "passive"))
      (node (ref "U5") (pin "26") (pinfunction "I2S_DIN_26") (pintype "passive"))
    )
    (net (code "173") (name "Net-(U5-I2S_DOUT)") (class "Default")
      (node (ref "R90") (pin "2") (pinfunction "2_2") (pintype "passive"))
      (node (ref "U5") (pin "25") (pinfunction "I2S_DOUT_25") (pintype "passive"))
    )
    (net (code "174") (name "Net-(U5-I2S_LRCLK)") (class "Default")
      (node (ref "R92") (pin "2") (pinfunction "2_2") (pintype "passive"))
      (node (ref "R93") (pin "2") (pinfunction "2_2") (pintype "passive"))
      (node (ref "U5") (pin "23") (pinfunction "I2S_LRCLK_23") (pintype "passive"))
    )
    (net (code "175") (name "Net-(U5-I2S_SCLK)") (class "Default")
      (node (ref "R94") (pin "2") (pinfunction "2_2") (pintype "passive"))
      (node (ref "R95") (pin "2") (pinfunction "2_2") (pintype "passive"))
      (node (ref "U5") (pin "24") (pinfunction "I2S_SCLK_24") (pintype "passive"))
    )
    (net (code "176") (name "Net-(U5-LINEIN_L)") (class "Default")
      (node (ref "C76") (pin "1") (pinfunction "1_1") (pintype "passive"))
      (node (ref "U5") (pin "14") (pinfunction "LINEIN_L_14") (pintype "passive"))
    )
    (net (code "177") (name "Net-(U5-LINEIN_R)") (class "Default")
      (node (ref "C75") (pin "1") (pinfunction "1_1") (pintype "passive"))
      (node (ref "U5") (pin "13") (pinfunction "LINEIN_R_13") (pintype "passive"))
    )
    (net (code "178") (name "Net-(U5-LINEOUT_R)") (class "Default")
      (node (ref "C61") (pin "2") (pinfunction "2_2") (pintype "passive"))
      (node (ref "U5") (pin "11") (pinfunction "LINEOUT_R_11") (pintype "passive"))
    )
    (net (code "179") (name "Net-(U5-MIC)") (class "Default")
      (node (ref "C65") (pin "1") (pinfunction "1_1") (pintype "passive"))
      (node (ref "U5") (pin "15") (pinfunction "MIC_15") (pintype "passive"))
    )
    (net (code "180") (name "Net-(U5-MIC_BIAS)") (class "Default")
      (node (ref "C66") (pin "1") (pinfunction "1_1") (pintype "passive"))
      (node (ref "U5") (pin "16") (pinfunction "MIC_BIAS_16") (pintype "passive"))
    )
    (net (code "181") (name "Net-(U5-SYS_MCLK)") (class "Default")
      (node (ref "R96") (pin "2") (pinfunction "2_2") (pintype "passive"))
      (node (ref "U5") (pin "21") (pinfunction "SYS_MCLK_21") (pintype "passive"))
    )
    (net (code "182") (name "Net-(U5-VAG)") (class "Default")
      (node (ref "C81") (pin "2") (pinfunction "2_2") (pintype "passive"))
      (node (ref "U5") (pin "10") (pinfunction "VAG_10") (pintype "passive"))
    )
    (net (code "183") (name "Net-(U5-VDDD)") (class "Default")
      (node (ref "C5") (pin "1") (pinfunction "1_1") (pintype "passive"))
      (node (ref "U5") (pin "30") (pinfunction "VDDD_30") (pintype "passive"))
    )
    (net (code "184") (name "Net-(U6-RDC)") (class "Default")
      (node (ref "C30") (pin "1") (pinfunction "1_1") (pintype "passive"))
      (node (ref "C31") (pin "2") (pintype "passive"))
      (node (ref "R48") (pin "2") (pinfunction "2_2") (pintype "passive"))
      (node (ref "U6") (pin "2") (pinfunction "TDC_2") (pintype "passive"))
      (node (ref "U6") (pin "7") (pinfunction "RDC_7") (pintype "passive"))
    )
    (net (code "185") (name "Net-(U6-RXC)") (class "Default")
      (node (ref "R54") (pin "1") (pinfunction "1_1") (pintype "passive"))
      (node (ref "U6") (pin "10") (pinfunction "RXC_10") (pintype "passive"))
    )
    (net (code "186") (name "Net-(U6-TXC)") (class "Default")
      (node (ref "R53") (pin "1") (pinfunction "1_1") (pintype "passive"))
      (node (ref "U6") (pin "15") (pinfunction "TXC_15") (pintype "passive"))
    )
    (net (code "187") (name "unconnected-(IC2-COL-Pad42)") (class "Default")
      (node (ref "IC2") (pin "42") (pinfunction "COL_42") (pintype "passive"))
    )
    (net (code "188") (name "unconnected-(IC2-LED_ACT-Pad26)") (class "Default")
      (node (ref "IC2") (pin "26") (pinfunction "LED_ACT_26") (pintype "passive"))
    )
    (net (code "189") (name "unconnected-(IC2-RESERVED-Pad8)") (class "Default")
      (node (ref "IC2") (pin "8") (pinfunction "RESERVED_8") (pintype "passive"))
    )
    (net (code "190") (name "unconnected-(IC2-RESERVED-Pad9)") (class "Default")
      (node (ref "IC2") (pin "9") (pinfunction "RESERVED_9") (pintype "passive"))
    )
    (net (code "191") (name "unconnected-(IC2-RESERVED-Pad10)") (class "Default")
      (node (ref "IC2") (pin "10") (pinfunction "RESERVED_10") (pintype "passive"))
    )
    (net (code "192") (name "unconnected-(IC2-RESERVED-Pad11)") (class "Default")
      (node (ref "IC2") (pin "11") (pinfunction "RESERVED_11") (pintype "passive"))
    )
    (net (code "193") (name "unconnected-(IC2-RESERVED-Pad12)") (class "Default")
      (node (ref "IC2") (pin "12") (pinfunction "RESERVED_12") (pintype "passive"))
    )
    (net (code "194") (name "unconnected-(IC2-RXD_2-Pad45)") (class "Default")
      (node (ref "IC2") (pin "45") (pinfunction "RXD_2_45") (pintype "passive"))
    )
    (net (code "195") (name "unconnected-(IC2-RXD_3-Pad46)") (class "Default")
      (node (ref "IC2") (pin "46") (pinfunction "RXD_3_46") (pintype "passive"))
    )
    (net (code "196") (name "unconnected-(IC2-RX_CLK-Pad38)") (class "Default")
      (node (ref "IC2") (pin "38") (pinfunction "RX_CLK_38") (pintype "passive"))
    )
    (net (code "197") (name "unconnected-(IC2-TXD_2-Pad5)") (class "Default")
      (node (ref "IC2") (pin "5") (pinfunction "TXD_2_5") (pintype "passive"))
    )
    (net (code "198") (name "unconnected-(IC2-TXD_3{slash}SNI_MODE-Pad6)") (class "Default")
      (node (ref "IC2") (pin "6") (pinfunction "TXD_3/SNI_MODE_6") (pintype "passive"))
    )
    (net (code "199") (name "unconnected-(IC2-TX_CLK-Pad1)") (class "Default")
      (node (ref "IC2") (pin "1") (pinfunction "TX_CLK_1") (pintype "passive"))
    )
    (net (code "200") (name "unconnected-(IC2-X2-Pad33)") (class "Default")
      (node (ref "IC2") (pin "33") (pinfunction "X2_33") (pintype "passive"))
    )
    (net (code "201") (name "unconnected-(IC2-XOUT-Pad25)") (class "Default")
      (node (ref "IC2") (pin "25") (pinfunction "XOUT_25") (pintype "passive"))
    )
    (net (code "202") (name "unconnected-(J2-Pad19)") (class "Default")
      (node (ref "J2") (pin "19") (pinfunction "19_19") (pintype "passive+no_connect"))
    )
    (net (code "203") (name "unconnected-(R4-Pad6)") (class "Default")
      (node (ref "R4") (pin "6") (pinfunction "6_6") (pintype "passive+no_connect"))
    )
    (net (code "204") (name "unconnected-(R17-Pad4)") (class "Default")
      (node (ref "R17") (pin "4") (pinfunction "4_4") (pintype "passive"))
    )
    (net (code "205") (name "unconnected-(R17-Pad5)") (class "Default")
      (node (ref "R17") (pin "5") (pinfunction "5_5") (pintype "passive"))
    )
    (net (code "206") (name "unconnected-(R26-Pad7)") (class "Default")
      (node (ref "R26") (pin "7") (pinfunction "7_7") (pintype "passive"))
    )
    (net (code "207") (name "unconnected-(R26-Pad8)") (class "Default")
      (node (ref "R26") (pin "8") (pinfunction "8_8") (pintype "passive"))
    )
    (net (code "208") (name "unconnected-(Re1-Pad2)") (class "Default")
      (node (ref "Re1") (pin "2") (pintype "passive"))
    )
    (net (code "209") (name "unconnected-(Re1-Pad3)") (class "Default")
      (node (ref "Re1") (pin "3") (pintype "passive"))
    )
    (net (code "210") (name "unconnected-(Re1-Pad4)") (class "Default")
      (node (ref "Re1") (pin "4") (pintype "passive"))
    )
    (net (code "211") (name "unconnected-(Re1-Pad7)") (class "Default")
      (node (ref "Re1") (pin "7") (pintype "passive"))
    )
    (net (code "212") (name "unconnected-(T4-Pad4)") (class "Default")
      (node (ref "T4") (pin "4") (pinfunction "4_4") (pintype "passive+no_connect"))
    )
    (net (code "213") (name "unconnected-(T5-Pad4)") (class "Default")
      (node (ref "T5") (pin "4") (pinfunction "4_4") (pintype "passive"))
    )
    (net (code "214") (name "unconnected-(U1-PA0-WKUP-Pad34)") (class "Default")
      (node (ref "U1") (pin "34") (pinfunction "PA0-WKUP_34") (pintype "passive"))
    )
    (net (code "215") (name "unconnected-(U1-PA6-Pad42)") (class "Default")
      (node (ref "U1") (pin "42") (pinfunction "PA6_42") (pintype "passive"))
    )
    (net (code "216") (name "unconnected-(U1-PA9-Pad101)") (class "Default")
      (node (ref "U1") (pin "101") (pinfunction "PA9_101") (pintype "passive"))
    )
    (net (code "217") (name "unconnected-(U1-PB0-Pad46)") (class "Default")
      (node (ref "U1") (pin "46") (pinfunction "PB0_46") (pintype "passive"))
    )
    (net (code "218") (name "unconnected-(U1-PB5-Pad135)") (class "Default")
      (node (ref "U1") (pin "135") (pinfunction "PB5_135") (pintype "passive"))
    )
    (net (code "219") (name "unconnected-(U1-PB10-Pad69)") (class "Default")
      (node (ref "U1") (pin "69") (pinfunction "PB10_69") (pintype "passive"))
    )
    (net (code "220") (name "unconnected-(U1-PB11-Pad70)") (class "Default")
      (node (ref "U1") (pin "70") (pinfunction "PB11_70") (pintype "passive"))
    )
    (net (code "221") (name "unconnected-(U1-PB14-Pad75)") (class "Default")
      (node (ref "U1") (pin "75") (pinfunction "PB14_75") (pintype "passive"))
    )
    (net (code "222") (name "unconnected-(U1-PC0-Pad26)") (class "Default")
      (node (ref "U1") (pin "26") (pinfunction "PC0_26") (pintype "passive"))
    )
    (net (code "223") (name "unconnected-(U1-PC2-Pad28)") (class "Default")
      (node (ref "U1") (pin "28") (pinfunction "PC2_28") (pintype "passive"))
    )
    (net (code "224") (name "unconnected-(U1-PC3-Pad29)") (class "Default")
      (node (ref "U1") (pin "29") (pinfunction "PC3_29") (pintype "passive"))
    )
    (net (code "225") (name "unconnected-(U1-PC6-Pad96)") (class "Default")
      (node (ref "U1") (pin "96") (pinfunction "PC6_96") (pintype "passive"))
    )
    (net (code "226") (name "unconnected-(U1-PC7-Pad97)") (class "Default")
      (node (ref "U1") (pin "97") (pinfunction "PC7_97") (pintype "passive"))
    )
    (net (code "227") (name "unconnected-(U1-PC8-Pad98)") (class "Default")
      (node (ref "U1") (pin "98") (pinfunction "PC8_98") (pintype "passive"))
    )
    (net (code "228") (name "unconnected-(U1-PC13-Pad7)") (class "Default")
      (node (ref "U1") (pin "7") (pinfunction "PC13_7") (pintype "passive"))
    )
    (net (code "229") (name "unconnected-(U1-PC14-OSC32_IN-Pad8)") (class "Default")
      (node (ref "U1") (pin "8") (pinfunction "PC14-OSC32_IN_8") (pintype "passive"))
    )
    (net (code "230") (name "unconnected-(U1-PC15-OSC32_OUT-Pad9)") (class "Default")
      (node (ref "U1") (pin "9") (pinfunction "PC15-OSC32_OUT_9") (pintype "passive"))
    )
    (net (code "231") (name "unconnected-(U1-PD7-Pad123)") (class "Default")
      (node (ref "U1") (pin "123") (pinfunction "PD7_123") (pintype "passive"))
    )
    (net (code "232") (name "unconnected-(U1-PD8-Pad77)") (class "Default")
      (node (ref "U1") (pin "77") (pinfunction "PD8_77") (pintype "passive"))
    )
    (net (code "233") (name "unconnected-(U1-PD9-Pad78)") (class "Default")
      (node (ref "U1") (pin "78") (pinfunction "PD9_78") (pintype "passive"))
    )
    (net (code "234") (name "unconnected-(U1-PD10-Pad79)") (class "Default")
      (node (ref "U1") (pin "79") (pinfunction "PD10_79") (pintype "passive"))
    )
    (net (code "235") (name "unconnected-(U1-PD11-Pad80)") (class "Default")
      (node (ref "U1") (pin "80") (pinfunction "PD11_80") (pintype "passive"))
    )
    (net (code "236") (name "unconnected-(U1-PD12-Pad81)") (class "Default")
      (node (ref "U1") (pin "81") (pinfunction "PD12_81") (pintype "passive"))
    )
    (net (code "237") (name "unconnected-(U1-PD13-Pad82)") (class "Default")
      (node (ref "U1") (pin "82") (pinfunction "PD13_82") (pintype "passive"))
    )
    (net (code "238") (name "unconnected-(U1-PD14-Pad85)") (class "Default")
      (node (ref "U1") (pin "85") (pinfunction "PD14_85") (pintype "passive"))
    )
    (net (code "239") (name "unconnected-(U1-PD15-Pad86)") (class "Default")
      (node (ref "U1") (pin "86") (pinfunction "PD15_86") (pintype "passive"))
    )
    (net (code "240") (name "unconnected-(U1-PE0-Pad141)") (class "Default")
      (node (ref "U1") (pin "141") (pinfunction "PE0_141") (pintype "passive"))
    )
    (net (code "241") (name "unconnected-(U1-PE1-Pad142)") (class "Default")
      (node (ref "U1") (pin "142") (pinfunction "PE1_142") (pintype "passive"))
    )
    (net (code "242") (name "unconnected-(U1-PE3-Pad2)") (class "Default")
      (node (ref "U1") (pin "2") (pinfunction "PE3_2") (pintype "passive"))
    )
    (net (code "243") (name "unconnected-(U1-PE4-Pad3)") (class "Default")
      (node (ref "U1") (pin "3") (pinfunction "PE4_3") (pintype "passive"))
    )
    (net (code "244") (name "unconnected-(U1-PE5-Pad4)") (class "Default")
      (node (ref "U1") (pin "4") (pinfunction "PE5_4") (pintype "passive"))
    )
    (net (code "245") (name "unconnected-(U1-PE6-Pad5)") (class "Default")
      (node (ref "U1") (pin "5") (pinfunction "PE6_5") (pintype "passive"))
    )
    (net (code "246") (name "unconnected-(U1-PE12-Pad65)") (class "Default")
      (node (ref "U1") (pin "65") (pinfunction "PE12_65") (pintype "passive"))
    )
    (net (code "247") (name "unconnected-(U1-PF2-Pad12)") (class "Default")
      (node (ref "U1") (pin "12") (pinfunction "PF2_12") (pintype "passive"))
    )
    (net (code "248") (name "unconnected-(U1-PF5-Pad15)") (class "Default")
      (node (ref "U1") (pin "15") (pinfunction "PF5_15") (pintype "passive"))
    )
    (net (code "249") (name "unconnected-(U1-PF6-Pad18)") (class "Default")
      (node (ref "U1") (pin "18") (pinfunction "PF6_18") (pintype "passive"))
    )
    (net (code "250") (name "unconnected-(U1-PF7-Pad19)") (class "Default")
      (node (ref "U1") (pin "19") (pinfunction "PF7_19") (pintype "passive"))
    )
    (net (code "251") (name "unconnected-(U1-PF8-Pad20)") (class "Default")
      (node (ref "U1") (pin "20") (pinfunction "PF8_20") (pintype "passive"))
    )
    (net (code "252") (name "unconnected-(U1-PF9-Pad21)") (class "Default")
      (node (ref "U1") (pin "21") (pinfunction "PF9_21") (pintype "passive"))
    )
    (net (code "253") (name "unconnected-(U1-PF10-Pad22)") (class "Default")
      (node (ref "U1") (pin "22") (pinfunction "PF10_22") (pintype "passive"))
    )
    (net (code "254") (name "unconnected-(U1-PG2-Pad87)") (class "Default")
      (node (ref "U1") (pin "87") (pinfunction "PG2_87") (pintype "passive"))
    )
    (net (code "255") (name "unconnected-(U1-PG3-Pad88)") (class "Default")
      (node (ref "U1") (pin "88") (pinfunction "PG3_88") (pintype "passive"))
    )
    (net (code "256") (name "unconnected-(U1-PG4-Pad89)") (class "Default")
      (node (ref "U1") (pin "89") (pinfunction "PG4_89") (pintype "passive"))
    )
    (net (code "257") (name "unconnected-(U1-PG5-Pad90)") (class "Default")
      (node (ref "U1") (pin "90") (pinfunction "PG5_90") (pintype "passive"))
    )
    (net (code "258") (name "unconnected-(U1-PG6-Pad91)") (class "Default")
      (node (ref "U1") (pin "91") (pinfunction "PG6_91") (pintype "passive"))
    )
    (net (code "259") (name "unconnected-(U1-PG7-Pad92)") (class "Default")
      (node (ref "U1") (pin "92") (pinfunction "PG7_92") (pintype "passive"))
    )
    (net (code "260") (name "unconnected-(U1-PG8-Pad93)") (class "Default")
      (node (ref "U1") (pin "93") (pinfunction "PG8_93") (pintype "passive"))
    )
    (net (code "261") (name "unconnected-(U1-PG9-Pad124)") (class "Default")
      (node (ref "U1") (pin "124") (pinfunction "PG9_124") (pintype "passive"))
    )
    (net (code "262") (name "unconnected-(U1-PG10-Pad125)") (class "Default")
      (node (ref "U1") (pin "125") (pinfunction "PG10_125") (pintype "passive"))
    )
    (net (code "263") (name "unconnected-(U1-PG12-Pad127)") (class "Default")
      (node (ref "U1") (pin "127") (pinfunction "PG12_127") (pintype "passive"))
    )
    (net (code "264") (name "unconnected-(U1-PG15-Pad132)") (class "Default")
      (node (ref "U1") (pin "132") (pinfunction "PG15_132") (pintype "passive"))
    )
    (net (code "265") (name "unconnected-(U1-RFU-Pad143)") (class "Default")
      (node (ref "U1") (pin "143") (pinfunction "RFU_143") (pintype "passive"))
    )
    (net (code "266") (name "unconnected-(U2-PFI-Pad4)") (class "Default")
      (node (ref "U2") (pin "4") (pinfunction "PFI_4") (pintype "passive+no_connect"))
    )
    (net (code "267") (name "unconnected-(U2-PFO-Pad5)") (class "Default")
      (node (ref "U2") (pin "5") (pinfunction "PFO_5") (pintype "passive+no_connect"))
    )
    (net (code "268") (name "unconnected-(U4-Pad4)") (class "Default")
      (node (ref "U4") (pin "4") (pinfunction "4_4") (pintype "passive+no_connect"))
    )
    (net (code "269") (name "unconnected-(U5-CPFILT-Pad18)") (class "Default")
      (node (ref "U5") (pin "18") (pinfunction "CPFILT_18") (pintype "passive"))
    )
    (net (code "270") (name "unconnected-(U5-HP_L-Pad6)") (class "Default")
      (node (ref "U5") (pin "6") (pinfunction "HP_L_6") (pintype "passive"))
    )
    (net (code "271") (name "unconnected-(U5-HP_R-Pad2)") (class "Default")
      (node (ref "U5") (pin "2") (pinfunction "HP_R_2") (pintype "passive"))
    )
    (net (code "272") (name "unconnected-(U5-HP_VGND-Pad4)") (class "Default")
      (node (ref "U5") (pin "4") (pinfunction "HP_VGND_4") (pintype "passive"))
    )
    (net (code "273") (name "unconnected-(U5-NC1-Pad8)") (class "Default")
      (node (ref "U5") (pin "8") (pinfunction "NC1_8") (pintype "passive"))
    )
    (net (code "274") (name "unconnected-(U5-NC2-Pad9)") (class "Default")
      (node (ref "U5") (pin "9") (pinfunction "NC2_9") (pintype "passive"))
    )
    (net (code "275") (name "unconnected-(U5-NC3-Pad17)") (class "Default")
      (node (ref "U5") (pin "17") (pinfunction "NC3_17") (pintype "passive"))
    )
    (net (code "276") (name "unconnected-(U5-NC4-Pad19)") (class "Default")
      (node (ref "U5") (pin "19") (pinfunction "NC4_19") (pintype "passive"))
    )
    (net (code "277") (name "unconnected-(U5-NC5-Pad22)") (class "Default")
      (node (ref "U5") (pin "22") (pinfunction "NC5_22") (pintype "passive"))
    )
    (net (code "278") (name "unconnected-(U5-NC6-Pad28)") (class "Default")
      (node (ref "U5") (pin "28") (pinfunction "NC6_28") (pintype "passive"))
    )
    (net (code "279") (name "unconnected-(U6-NC-Pad4)") (class "Default")
      (node (ref "U6") (pin "4") (pinfunction "NC_4") (pintype "passive"))
    )
    (net (code "280") (name "unconnected-(U6-NC-Pad5)") (class "Default")
      (node (ref "U6") (pin "5") (pinfunction "NC_5") (pintype "passive"))
    )
    (net (code "281") (name "unconnected-(U6-NC-Pad12)") (class "Default")
      (node (ref "U6") (pin "12") (pinfunction "NC_12") (pintype "passive"))
    )
    (net (code "282") (name "unconnected-(U6-NC-Pad13)") (class "Default")
      (node (ref "U6") (pin "13") (pinfunction "NC_13") (pintype "passive"))
    )
    (net (code "283") (name "unconnected-(U8-Pad4)") (class "Default")
      (node (ref "U8") (pin "4") (pinfunction "4_4") (pintype "passive+no_connect"))
    )
    (net (code "284") (name "unconnected-(Y1-NC-Pad1)") (class "Default")
      (node (ref "Y1") (pin "1") (pinfunction "NC_1") (pintype "passive"))
    )
    (net (code "285") (name "unconnected-(Y2-NC-Pad1)") (class "Default")
      (node (ref "Y2") (pin "1") (pinfunction "NC_1") (pintype "passive"))
    )
  )
)
